# qdr2_3.net
KiCad netlist of a schematic drawn in Altium Designer
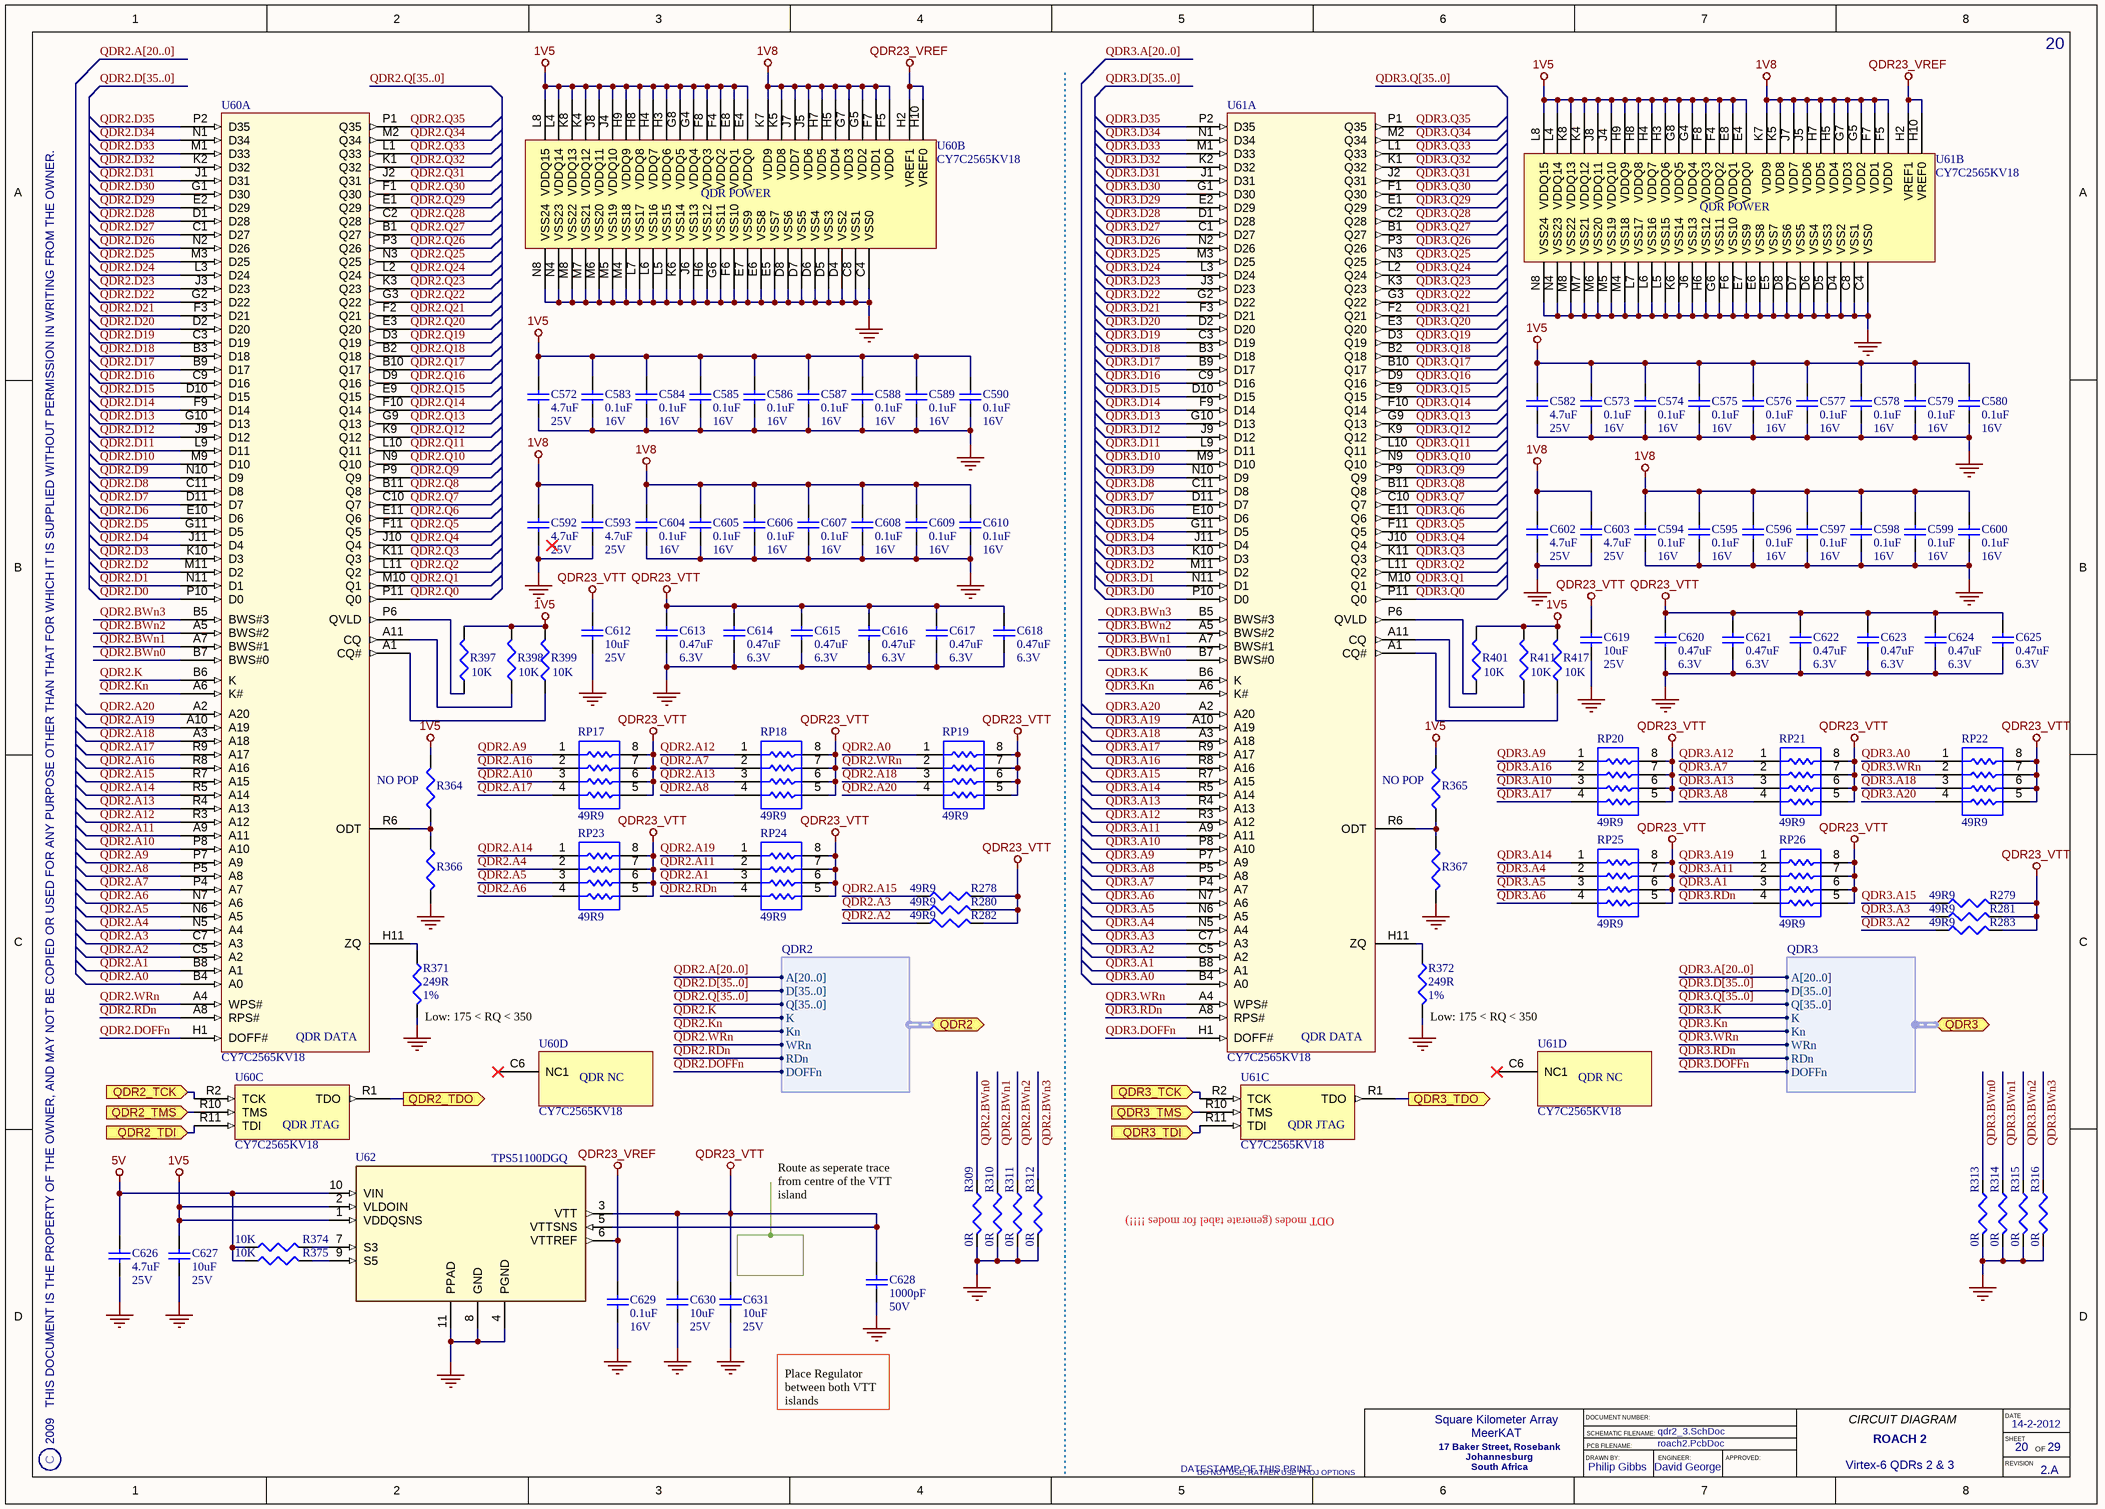
[diagram p0: qdr2_3.SchDoc]

(export (version "E")
  (design (tool "Eeschema 10.0.6"))
  (components
    (comp (ref "C572")
      (value "4.7uF")
      (footprint "CAPC2012X127L")
      (description "4.7uF, Ceramic Capacitor")
      (fields
        (field (name "RATING") "25V")
        (field (name "MANUFACTURER") "MURATA")
        (field (name "PARTNUM") "GRM21BR61E475KA12K")
      )
      (libsource (lib "altium_db") (part "CapStd"))
    )
    (comp (ref "C573")
      (value "0.1uF")
      (footprint "CAPC1005X60L")
      (description "0.1uF, Ceramic Capacitor")
      (fields
        (field (name "RATING") "16V")
        (field (name "MANUFACTURER") "VENKEL")
        (field (name "PARTNUM") "C0402X7R160-104KN")
      )
      (libsource (lib "altium_db") (part "CapStd"))
    )
    (comp (ref "C574")
      (value "0.1uF")
      (footprint "CAPC1005X60L")
      (description "0.1uF, Ceramic Capacitor")
      (fields
        (field (name "RATING") "16V")
        (field (name "MANUFACTURER") "VENKEL")
        (field (name "PARTNUM") "C0402X7R160-104KN")
      )
      (libsource (lib "altium_db") (part "CapStd"))
    )
    (comp (ref "C575")
      (value "0.1uF")
      (footprint "CAPC1005X60L")
      (description "0.1uF, Ceramic Capacitor")
      (fields
        (field (name "RATING") "16V")
        (field (name "MANUFACTURER") "VENKEL")
        (field (name "PARTNUM") "C0402X7R160-104KN")
      )
      (libsource (lib "altium_db") (part "CapStd"))
    )
    (comp (ref "C576")
      (value "0.1uF")
      (footprint "CAPC1005X60L")
      (description "0.1uF, Ceramic Capacitor")
      (fields
        (field (name "RATING") "16V")
        (field (name "MANUFACTURER") "VENKEL")
        (field (name "PARTNUM") "C0402X7R160-104KN")
      )
      (libsource (lib "altium_db") (part "CapStd"))
    )
    (comp (ref "C577")
      (value "0.1uF")
      (footprint "CAPC1005X60L")
      (description "0.1uF, Ceramic Capacitor")
      (fields
        (field (name "RATING") "16V")
        (field (name "MANUFACTURER") "VENKEL")
        (field (name "PARTNUM") "C0402X7R160-104KN")
      )
      (libsource (lib "altium_db") (part "CapStd"))
    )
    (comp (ref "C578")
      (value "0.1uF")
      (footprint "CAPC1005X60L")
      (description "0.1uF, Ceramic Capacitor")
      (fields
        (field (name "RATING") "16V")
        (field (name "MANUFACTURER") "VENKEL")
        (field (name "PARTNUM") "C0402X7R160-104KN")
      )
      (libsource (lib "altium_db") (part "CapStd"))
    )
    (comp (ref "C579")
      (value "0.1uF")
      (footprint "CAPC1005X60L")
      (description "0.1uF, Ceramic Capacitor")
      (fields
        (field (name "RATING") "16V")
        (field (name "MANUFACTURER") "VENKEL")
        (field (name "PARTNUM") "C0402X7R160-104KN")
      )
      (libsource (lib "altium_db") (part "CapStd"))
    )
    (comp (ref "C580")
      (value "0.1uF")
      (footprint "CAPC1005X60L")
      (description "0.1uF, Ceramic Capacitor")
      (fields
        (field (name "RATING") "16V")
        (field (name "MANUFACTURER") "VENKEL")
        (field (name "PARTNUM") "C0402X7R160-104KN")
      )
      (libsource (lib "altium_db") (part "CapStd"))
    )
    (comp (ref "C582")
      (value "4.7uF")
      (footprint "CAPC2012X127L")
      (description "4.7uF, Ceramic Capacitor")
      (fields
        (field (name "RATING") "25V")
        (field (name "MANUFACTURER") "MURATA")
        (field (name "PARTNUM") "GRM21BR61E475KA12K")
      )
      (libsource (lib "altium_db") (part "CapStd"))
    )
    (comp (ref "C583")
      (value "0.1uF")
      (footprint "CAPC1005X60L")
      (description "0.1uF, Ceramic Capacitor")
      (fields
        (field (name "RATING") "16V")
        (field (name "MANUFACTURER") "VENKEL")
        (field (name "PARTNUM") "C0402X7R160-104KN")
      )
      (libsource (lib "altium_db") (part "CapStd"))
    )
    (comp (ref "C584")
      (value "0.1uF")
      (footprint "CAPC1005X60L")
      (description "0.1uF, Ceramic Capacitor")
      (fields
        (field (name "RATING") "16V")
        (field (name "MANUFACTURER") "VENKEL")
        (field (name "PARTNUM") "C0402X7R160-104KN")
      )
      (libsource (lib "altium_db") (part "CapStd"))
    )
    (comp (ref "C585")
      (value "0.1uF")
      (footprint "CAPC1005X60L")
      (description "0.1uF, Ceramic Capacitor")
      (fields
        (field (name "RATING") "16V")
        (field (name "MANUFACTURER") "VENKEL")
        (field (name "PARTNUM") "C0402X7R160-104KN")
      )
      (libsource (lib "altium_db") (part "CapStd"))
    )
    (comp (ref "C586")
      (value "0.1uF")
      (footprint "CAPC1005X60L")
      (description "0.1uF, Ceramic Capacitor")
      (fields
        (field (name "RATING") "16V")
        (field (name "MANUFACTURER") "VENKEL")
        (field (name "PARTNUM") "C0402X7R160-104KN")
      )
      (libsource (lib "altium_db") (part "CapStd"))
    )
    (comp (ref "C587")
      (value "0.1uF")
      (footprint "CAPC1005X60L")
      (description "0.1uF, Ceramic Capacitor")
      (fields
        (field (name "RATING") "16V")
        (field (name "MANUFACTURER") "VENKEL")
        (field (name "PARTNUM") "C0402X7R160-104KN")
      )
      (libsource (lib "altium_db") (part "CapStd"))
    )
    (comp (ref "C588")
      (value "0.1uF")
      (footprint "CAPC1005X60L")
      (description "0.1uF, Ceramic Capacitor")
      (fields
        (field (name "RATING") "16V")
        (field (name "MANUFACTURER") "VENKEL")
        (field (name "PARTNUM") "C0402X7R160-104KN")
      )
      (libsource (lib "altium_db") (part "CapStd"))
    )
    (comp (ref "C589")
      (value "0.1uF")
      (footprint "CAPC1005X60L")
      (description "0.1uF, Ceramic Capacitor")
      (fields
        (field (name "RATING") "16V")
        (field (name "MANUFACTURER") "VENKEL")
        (field (name "PARTNUM") "C0402X7R160-104KN")
      )
      (libsource (lib "altium_db") (part "CapStd"))
    )
    (comp (ref "C590")
      (value "0.1uF")
      (footprint "CAPC1005X60L")
      (description "0.1uF, Ceramic Capacitor")
      (fields
        (field (name "RATING") "16V")
        (field (name "MANUFACTURER") "VENKEL")
        (field (name "PARTNUM") "C0402X7R160-104KN")
      )
      (libsource (lib "altium_db") (part "CapStd"))
    )
    (comp (ref "C592")
      (value "4.7uF")
      (footprint "CAPC2012X127L")
      (description "4.7uF, Ceramic Capacitor")
      (fields
        (field (name "RATING") "25V")
        (field (name "MANUFACTURER") "MURATA")
        (field (name "PARTNUM") "GRM21BR61E475KA12K")
      )
      (libsource (lib "altium_db") (part "CapStd"))
    )
    (comp (ref "C593")
      (value "4.7uF")
      (footprint "CAPC2012X127L")
      (description "4.7uF, Ceramic Capacitor")
      (fields
        (field (name "RATING") "25V")
        (field (name "MANUFACTURER") "MURATA")
        (field (name "PARTNUM") "GRM21BR61E475KA12K")
      )
      (libsource (lib "altium_db") (part "CapStd"))
    )
    (comp (ref "C594")
      (value "0.1uF")
      (footprint "CAPC1005X60L")
      (description "0.1uF, Ceramic Capacitor")
      (fields
        (field (name "RATING") "16V")
        (field (name "MANUFACTURER") "VENKEL")
        (field (name "PARTNUM") "C0402X7R160-104KN")
      )
      (libsource (lib "altium_db") (part "CapStd"))
    )
    (comp (ref "C595")
      (value "0.1uF")
      (footprint "CAPC1005X60L")
      (description "0.1uF, Ceramic Capacitor")
      (fields
        (field (name "RATING") "16V")
        (field (name "MANUFACTURER") "VENKEL")
        (field (name "PARTNUM") "C0402X7R160-104KN")
      )
      (libsource (lib "altium_db") (part "CapStd"))
    )
    (comp (ref "C596")
      (value "0.1uF")
      (footprint "CAPC1005X60L")
      (description "0.1uF, Ceramic Capacitor")
      (fields
        (field (name "RATING") "16V")
        (field (name "MANUFACTURER") "VENKEL")
        (field (name "PARTNUM") "C0402X7R160-104KN")
      )
      (libsource (lib "altium_db") (part "CapStd"))
    )
    (comp (ref "C597")
      (value "0.1uF")
      (footprint "CAPC1005X60L")
      (description "0.1uF, Ceramic Capacitor")
      (fields
        (field (name "RATING") "16V")
        (field (name "MANUFACTURER") "VENKEL")
        (field (name "PARTNUM") "C0402X7R160-104KN")
      )
      (libsource (lib "altium_db") (part "CapStd"))
    )
    (comp (ref "C598")
      (value "0.1uF")
      (footprint "CAPC1005X60L")
      (description "0.1uF, Ceramic Capacitor")
      (fields
        (field (name "RATING") "16V")
        (field (name "MANUFACTURER") "VENKEL")
        (field (name "PARTNUM") "C0402X7R160-104KN")
      )
      (libsource (lib "altium_db") (part "CapStd"))
    )
    (comp (ref "C599")
      (value "0.1uF")
      (footprint "CAPC1005X60L")
      (description "0.1uF, Ceramic Capacitor")
      (fields
        (field (name "RATING") "16V")
        (field (name "MANUFACTURER") "VENKEL")
        (field (name "PARTNUM") "C0402X7R160-104KN")
      )
      (libsource (lib "altium_db") (part "CapStd"))
    )
    (comp (ref "C600")
      (value "0.1uF")
      (footprint "CAPC1005X60L")
      (description "0.1uF, Ceramic Capacitor")
      (fields
        (field (name "RATING") "16V")
        (field (name "MANUFACTURER") "VENKEL")
        (field (name "PARTNUM") "C0402X7R160-104KN")
      )
      (libsource (lib "altium_db") (part "CapStd"))
    )
    (comp (ref "C602")
      (value "4.7uF")
      (footprint "CAPC2012X127L")
      (description "4.7uF, Ceramic Capacitor")
      (fields
        (field (name "RATING") "25V")
        (field (name "MANUFACTURER") "MURATA")
        (field (name "PARTNUM") "GRM21BR61E475KA12K")
      )
      (libsource (lib "altium_db") (part "CapStd"))
    )
    (comp (ref "C603")
      (value "4.7uF")
      (footprint "CAPC2012X127L")
      (description "4.7uF, Ceramic Capacitor")
      (fields
        (field (name "RATING") "25V")
        (field (name "MANUFACTURER") "MURATA")
        (field (name "PARTNUM") "GRM21BR61E475KA12K")
      )
      (libsource (lib "altium_db") (part "CapStd"))
    )
    (comp (ref "C604")
      (value "0.1uF")
      (footprint "CAPC1005X60L")
      (description "0.1uF, Ceramic Capacitor")
      (fields
        (field (name "RATING") "16V")
        (field (name "MANUFACTURER") "VENKEL")
        (field (name "PARTNUM") "C0402X7R160-104KN")
      )
      (libsource (lib "altium_db") (part "CapStd"))
    )
    (comp (ref "C605")
      (value "0.1uF")
      (footprint "CAPC1005X60L")
      (description "0.1uF, Ceramic Capacitor")
      (fields
        (field (name "RATING") "16V")
        (field (name "MANUFACTURER") "VENKEL")
        (field (name "PARTNUM") "C0402X7R160-104KN")
      )
      (libsource (lib "altium_db") (part "CapStd"))
    )
    (comp (ref "C606")
      (value "0.1uF")
      (footprint "CAPC1005X60L")
      (description "0.1uF, Ceramic Capacitor")
      (fields
        (field (name "RATING") "16V")
        (field (name "MANUFACTURER") "VENKEL")
        (field (name "PARTNUM") "C0402X7R160-104KN")
      )
      (libsource (lib "altium_db") (part "CapStd"))
    )
    (comp (ref "C607")
      (value "0.1uF")
      (footprint "CAPC1005X60L")
      (description "0.1uF, Ceramic Capacitor")
      (fields
        (field (name "RATING") "16V")
        (field (name "MANUFACTURER") "VENKEL")
        (field (name "PARTNUM") "C0402X7R160-104KN")
      )
      (libsource (lib "altium_db") (part "CapStd"))
    )
    (comp (ref "C608")
      (value "0.1uF")
      (footprint "CAPC1005X60L")
      (description "0.1uF, Ceramic Capacitor")
      (fields
        (field (name "RATING") "16V")
        (field (name "MANUFACTURER") "VENKEL")
        (field (name "PARTNUM") "C0402X7R160-104KN")
      )
      (libsource (lib "altium_db") (part "CapStd"))
    )
    (comp (ref "C609")
      (value "0.1uF")
      (footprint "CAPC1005X60L")
      (description "0.1uF, Ceramic Capacitor")
      (fields
        (field (name "RATING") "16V")
        (field (name "MANUFACTURER") "VENKEL")
        (field (name "PARTNUM") "C0402X7R160-104KN")
      )
      (libsource (lib "altium_db") (part "CapStd"))
    )
    (comp (ref "C610")
      (value "0.1uF")
      (footprint "CAPC1005X60L")
      (description "0.1uF, Ceramic Capacitor")
      (fields
        (field (name "RATING") "16V")
        (field (name "MANUFACTURER") "VENKEL")
        (field (name "PARTNUM") "C0402X7R160-104KN")
      )
      (libsource (lib "altium_db") (part "CapStd"))
    )
    (comp (ref "C612")
      (value "10uF")
      (footprint "CAPC3225X200L")
      (description "10uF, Ceramic Capacitor")
      (fields
        (field (name "RATING") "25V")
        (field (name "MANUFACTURER") "MURATA")
        (field (name "PARTNUM") "GRM32DR61E106KA12L")
      )
      (libsource (lib "altium_db") (part "CapStd"))
    )
    (comp (ref "C613")
      (value "0.47uF")
      (footprint "CAPC1005X55L")
      (description "0.47uF, Ceramic Capacitor")
      (fields
        (field (name "RATING") "6.3V")
        (field (name "MANUFACTURER") "MURATA")
        (field (name "PARTNUM") "GRM155R60J474KE19")
      )
      (libsource (lib "altium_db") (part "CapStd"))
    )
    (comp (ref "C614")
      (value "0.47uF")
      (footprint "CAPC1005X55L")
      (description "0.47uF, Ceramic Capacitor")
      (fields
        (field (name "RATING") "6.3V")
        (field (name "MANUFACTURER") "MURATA")
        (field (name "PARTNUM") "GRM155R60J474KE19")
      )
      (libsource (lib "altium_db") (part "CapStd"))
    )
    (comp (ref "C615")
      (value "0.47uF")
      (footprint "CAPC1005X55L")
      (description "0.47uF, Ceramic Capacitor")
      (fields
        (field (name "RATING") "6.3V")
        (field (name "MANUFACTURER") "MURATA")
        (field (name "PARTNUM") "GRM155R60J474KE19")
      )
      (libsource (lib "altium_db") (part "CapStd"))
    )
    (comp (ref "C616")
      (value "0.47uF")
      (footprint "CAPC1005X55L")
      (description "0.47uF, Ceramic Capacitor")
      (fields
        (field (name "RATING") "6.3V")
        (field (name "MANUFACTURER") "MURATA")
        (field (name "PARTNUM") "GRM155R60J474KE19")
      )
      (libsource (lib "altium_db") (part "CapStd"))
    )
    (comp (ref "C617")
      (value "0.47uF")
      (footprint "CAPC1005X55L")
      (description "0.47uF, Ceramic Capacitor")
      (fields
        (field (name "RATING") "6.3V")
        (field (name "MANUFACTURER") "MURATA")
        (field (name "PARTNUM") "GRM155R60J474KE19")
      )
      (libsource (lib "altium_db") (part "CapStd"))
    )
    (comp (ref "C618")
      (value "0.47uF")
      (footprint "CAPC1005X55L")
      (description "0.47uF, Ceramic Capacitor")
      (fields
        (field (name "RATING") "6.3V")
        (field (name "MANUFACTURER") "MURATA")
        (field (name "PARTNUM") "GRM155R60J474KE19")
      )
      (libsource (lib "altium_db") (part "CapStd"))
    )
    (comp (ref "C619")
      (value "10uF")
      (footprint "CAPC3225X200L")
      (description "10uF, Ceramic Capacitor")
      (fields
        (field (name "RATING") "25V")
        (field (name "MANUFACTURER") "MURATA")
        (field (name "PARTNUM") "GRM32DR61E106KA12L")
      )
      (libsource (lib "altium_db") (part "CapStd"))
    )
    (comp (ref "C620")
      (value "0.47uF")
      (footprint "CAPC1005X55L")
      (description "0.47uF, Ceramic Capacitor")
      (fields
        (field (name "RATING") "6.3V")
        (field (name "MANUFACTURER") "MURATA")
        (field (name "PARTNUM") "GRM155R60J474KE19")
      )
      (libsource (lib "altium_db") (part "CapStd"))
    )
    (comp (ref "C621")
      (value "0.47uF")
      (footprint "CAPC1005X55L")
      (description "0.47uF, Ceramic Capacitor")
      (fields
        (field (name "RATING") "6.3V")
        (field (name "MANUFACTURER") "MURATA")
        (field (name "PARTNUM") "GRM155R60J474KE19")
      )
      (libsource (lib "altium_db") (part "CapStd"))
    )
    (comp (ref "C622")
      (value "0.47uF")
      (footprint "CAPC1005X55L")
      (description "0.47uF, Ceramic Capacitor")
      (fields
        (field (name "RATING") "6.3V")
        (field (name "MANUFACTURER") "MURATA")
        (field (name "PARTNUM") "GRM155R60J474KE19")
      )
      (libsource (lib "altium_db") (part "CapStd"))
    )
    (comp (ref "C623")
      (value "0.47uF")
      (footprint "CAPC1005X55L")
      (description "0.47uF, Ceramic Capacitor")
      (fields
        (field (name "RATING") "6.3V")
        (field (name "MANUFACTURER") "MURATA")
        (field (name "PARTNUM") "GRM155R60J474KE19")
      )
      (libsource (lib "altium_db") (part "CapStd"))
    )
    (comp (ref "C624")
      (value "0.47uF")
      (footprint "CAPC1005X55L")
      (description "0.47uF, Ceramic Capacitor")
      (fields
        (field (name "RATING") "6.3V")
        (field (name "MANUFACTURER") "MURATA")
        (field (name "PARTNUM") "GRM155R60J474KE19")
      )
      (libsource (lib "altium_db") (part "CapStd"))
    )
    (comp (ref "C625")
      (value "0.47uF")
      (footprint "CAPC1005X55L")
      (description "0.47uF, Ceramic Capacitor")
      (fields
        (field (name "RATING") "6.3V")
        (field (name "MANUFACTURER") "MURATA")
        (field (name "PARTNUM") "GRM155R60J474KE19")
      )
      (libsource (lib "altium_db") (part "CapStd"))
    )
    (comp (ref "C626")
      (value "4.7uF")
      (footprint "CAPC2012X127L")
      (description "4.7uF, Ceramic Capacitor")
      (fields
        (field (name "RATING") "25V")
        (field (name "MANUFACTURER") "MURATA")
        (field (name "PARTNUM") "GRM21BR61E475KA12K")
      )
      (libsource (lib "altium_db") (part "CapStd"))
    )
    (comp (ref "C627")
      (value "10uF")
      (footprint "CAPC3225X200L")
      (description "10uF, Ceramic Capacitor")
      (fields
        (field (name "RATING") "25V")
        (field (name "MANUFACTURER") "MURATA")
        (field (name "PARTNUM") "GRM32DR61E106KA12L")
      )
      (libsource (lib "altium_db") (part "CapStd"))
    )
    (comp (ref "C628")
      (value "1000pF")
      (footprint "CAPC1005X55L")
      (description "1000pF, Ceramic Capacitor")
      (fields
        (field (name "RATING") "50V")
        (field (name "MANUFACTURER") "MURATA")
        (field (name "PARTNUM") "GRM155R61H102KA01D")
      )
      (libsource (lib "altium_db") (part "CapStd"))
    )
    (comp (ref "C629")
      (value "0.1uF")
      (footprint "CAPC1005X60L")
      (description "0.1uF, Ceramic Capacitor")
      (fields
        (field (name "RATING") "16V")
        (field (name "MANUFACTURER") "VENKEL")
        (field (name "PARTNUM") "C0402X7R160-104KN")
      )
      (libsource (lib "altium_db") (part "CapStd"))
    )
    (comp (ref "C630")
      (value "10uF")
      (footprint "CAPC3225X200L")
      (description "10uF, Ceramic Capacitor")
      (fields
        (field (name "RATING") "25V")
        (field (name "MANUFACTURER") "MURATA")
        (field (name "PARTNUM") "GRM32DR61E106KA12L")
      )
      (libsource (lib "altium_db") (part "CapStd"))
    )
    (comp (ref "C631")
      (value "10uF")
      (footprint "CAPC3225X200L")
      (description "10uF, Ceramic Capacitor")
      (fields
        (field (name "RATING") "25V")
        (field (name "MANUFACTURER") "MURATA")
        (field (name "PARTNUM") "GRM32DR61E106KA12L")
      )
      (libsource (lib "altium_db") (part "CapStd"))
    )
    (comp (ref "R278")
      (value "49R9")
      (footprint "RESC1005X40L")
      (description "49R9, 1.1mm x 0.5mm, Thick Film Resistor")
      (fields (field (name "MANUFACTURER") "ROYALOHM") (field (name "PARTNUM") "0402WGF499JT1E"))
      (libsource (lib "altium_db") (part "ResStd"))
    )
    (comp (ref "R279")
      (value "49R9")
      (footprint "RESC1005X40L")
      (description "49R9, 1.1mm x 0.5mm, Thick Film Resistor")
      (fields (field (name "MANUFACTURER") "ROYALOHM") (field (name "PARTNUM") "0402WGF499JT1E"))
      (libsource (lib "altium_db") (part "ResStd"))
    )
    (comp (ref "R280")
      (value "49R9")
      (footprint "RESC1005X40L")
      (description "49R9, 1.1mm x 0.5mm, Thick Film Resistor")
      (fields (field (name "MANUFACTURER") "ROYALOHM") (field (name "PARTNUM") "0402WGF499JT1E"))
      (libsource (lib "altium_db") (part "ResStd"))
    )
    (comp (ref "R281")
      (value "49R9")
      (footprint "RESC1005X40L")
      (description "49R9, 1.1mm x 0.5mm, Thick Film Resistor")
      (fields (field (name "MANUFACTURER") "ROYALOHM") (field (name "PARTNUM") "0402WGF499JT1E"))
      (libsource (lib "altium_db") (part "ResStd"))
    )
    (comp (ref "R282")
      (value "49R9")
      (footprint "RESC1005X40L")
      (description "49R9, 1.1mm x 0.5mm, Thick Film Resistor")
      (fields (field (name "MANUFACTURER") "ROYALOHM") (field (name "PARTNUM") "0402WGF499JT1E"))
      (libsource (lib "altium_db") (part "ResStd"))
    )
    (comp (ref "R283")
      (value "49R9")
      (footprint "RESC1005X40L")
      (description "49R9, 1.1mm x 0.5mm, Thick Film Resistor")
      (fields (field (name "MANUFACTURER") "ROYALOHM") (field (name "PARTNUM") "0402WGF499JT1E"))
      (libsource (lib "altium_db") (part "ResStd"))
    )
    (comp (ref "R309")
      (value "0R")
      (footprint "RESC1005X40L")
      (description "0R, 1.1mm x 0.5mm, Thick Film Resistor")
      (fields (field (name "MANUFACTURER") "ROYALOHM") (field (name "PARTNUM") "0402WG00000T1E"))
      (libsource (lib "altium_db") (part "ResStd"))
    )
    (comp (ref "R310")
      (value "0R")
      (footprint "RESC1005X40L")
      (description "0R, 1.1mm x 0.5mm, Thick Film Resistor")
      (fields (field (name "MANUFACTURER") "ROYALOHM") (field (name "PARTNUM") "0402WG00000T1E"))
      (libsource (lib "altium_db") (part "ResStd"))
    )
    (comp (ref "R311")
      (value "0R")
      (footprint "RESC1005X40L")
      (description "0R, 1.1mm x 0.5mm, Thick Film Resistor")
      (fields (field (name "MANUFACTURER") "ROYALOHM") (field (name "PARTNUM") "0402WG00000T1E"))
      (libsource (lib "altium_db") (part "ResStd"))
    )
    (comp (ref "R312")
      (value "0R")
      (footprint "RESC1005X40L")
      (description "0R, 1.1mm x 0.5mm, Thick Film Resistor")
      (fields (field (name "MANUFACTURER") "ROYALOHM") (field (name "PARTNUM") "0402WG00000T1E"))
      (libsource (lib "altium_db") (part "ResStd"))
    )
    (comp (ref "R313")
      (value "0R")
      (footprint "RESC1005X40L")
      (description "0R, 1.1mm x 0.5mm, Thick Film Resistor")
      (fields (field (name "MANUFACTURER") "ROYALOHM") (field (name "PARTNUM") "0402WG00000T1E"))
      (libsource (lib "altium_db") (part "ResStd"))
    )
    (comp (ref "R314")
      (value "0R")
      (footprint "RESC1005X40L")
      (description "0R, 1.1mm x 0.5mm, Thick Film Resistor")
      (fields (field (name "MANUFACTURER") "ROYALOHM") (field (name "PARTNUM") "0402WG00000T1E"))
      (libsource (lib "altium_db") (part "ResStd"))
    )
    (comp (ref "R315")
      (value "0R")
      (footprint "RESC1005X40L")
      (description "0R, 1.1mm x 0.5mm, Thick Film Resistor")
      (fields (field (name "MANUFACTURER") "ROYALOHM") (field (name "PARTNUM") "0402WG00000T1E"))
      (libsource (lib "altium_db") (part "ResStd"))
    )
    (comp (ref "R316")
      (value "0R")
      (footprint "RESC1005X40L")
      (description "0R, 1.1mm x 0.5mm, Thick Film Resistor")
      (fields (field (name "MANUFACTURER") "ROYALOHM") (field (name "PARTNUM") "0402WG00000T1E"))
      (libsource (lib "altium_db") (part "ResStd"))
    )
    (comp (ref "R364")
      (value "10K")
      (footprint "RESC1005X40L")
      (description "10K, 1.1mm x 0.5mm, Thick Film Resistor")
      (fields (field (name "MANUFACTURER") "ROYALOHM") (field (name "PARTNUM") "0402WGJ0103T1E"))
      (libsource (lib "altium_db") (part "ResStd"))
    )
    (comp (ref "R365")
      (value "10K")
      (footprint "RESC1005X40L")
      (description "10K, 1.1mm x 0.5mm, Thick Film Resistor")
      (fields (field (name "MANUFACTURER") "ROYALOHM") (field (name "PARTNUM") "0402WGJ0103T1E"))
      (libsource (lib "altium_db") (part "ResStd"))
    )
    (comp (ref "R366")
      (value "10K")
      (footprint "RESC1005X40L")
      (description "10K, 1.1mm x 0.5mm, Thick Film Resistor")
      (fields (field (name "MANUFACTURER") "ROYALOHM") (field (name "PARTNUM") "0402WGJ0103T1E"))
      (libsource (lib "altium_db") (part "ResStd"))
    )
    (comp (ref "R367")
      (value "10K")
      (footprint "RESC1005X40L")
      (description "10K, 1.1mm x 0.5mm, Thick Film Resistor")
      (fields (field (name "MANUFACTURER") "ROYALOHM") (field (name "PARTNUM") "0402WGJ0103T1E"))
      (libsource (lib "altium_db") (part "ResStd"))
    )
    (comp (ref "R371")
      (value "249R")
      (footprint "RESC1005X40L")
      (description "249R, 1.1mm x 0.5mm, Thick Film Resistor")
      (fields
        (field (name "MANUFACTURER") "ROYALOHM")
        (field (name "PARTNUM") "0402WGF2490T1E")
        (field (name "TOLERANCE") "1%")
      )
      (libsource (lib "altium_db") (part "ResStd"))
    )
    (comp (ref "R372")
      (value "249R")
      (footprint "RESC1005X40L")
      (description "249R, 1.1mm x 0.5mm, Thick Film Resistor")
      (fields
        (field (name "MANUFACTURER") "ROYALOHM")
        (field (name "PARTNUM") "0402WGF2490T1E")
        (field (name "TOLERANCE") "1%")
      )
      (libsource (lib "altium_db") (part "ResStd"))
    )
    (comp (ref "R374")
      (value "10K")
      (footprint "RESC1005X40L")
      (description "10K, 1.1mm x 0.5mm, Thick Film Resistor")
      (fields (field (name "MANUFACTURER") "ROYALOHM") (field (name "PARTNUM") "0402WGJ0103T1E"))
      (libsource (lib "altium_db") (part "ResStd"))
    )
    (comp (ref "R375")
      (value "10K")
      (footprint "RESC1005X40L")
      (description "10K, 1.1mm x 0.5mm, Thick Film Resistor")
      (fields (field (name "MANUFACTURER") "ROYALOHM") (field (name "PARTNUM") "0402WGJ0103T1E"))
      (libsource (lib "altium_db") (part "ResStd"))
    )
    (comp (ref "R397")
      (value "10K")
      (footprint "RESC1005X40L")
      (description "10K, 1.1mm x 0.5mm, Thick Film Resistor")
      (fields (field (name "MANUFACTURER") "ROYALOHM") (field (name "PARTNUM") "0402WGJ0103T1E"))
      (libsource (lib "altium_db") (part "ResStd"))
    )
    (comp (ref "R398")
      (value "10K")
      (footprint "RESC1005X40L")
      (description "10K, 1.1mm x 0.5mm, Thick Film Resistor")
      (fields (field (name "MANUFACTURER") "ROYALOHM") (field (name "PARTNUM") "0402WGJ0103T1E"))
      (libsource (lib "altium_db") (part "ResStd"))
    )
    (comp (ref "R399")
      (value "10K")
      (footprint "RESC1005X40L")
      (description "10K, 1.1mm x 0.5mm, Thick Film Resistor")
      (fields (field (name "MANUFACTURER") "ROYALOHM") (field (name "PARTNUM") "0402WGJ0103T1E"))
      (libsource (lib "altium_db") (part "ResStd"))
    )
    (comp (ref "R401")
      (value "10K")
      (footprint "RESC1005X40L")
      (description "10K, 1.1mm x 0.5mm, Thick Film Resistor")
      (fields (field (name "MANUFACTURER") "ROYALOHM") (field (name "PARTNUM") "0402WGJ0103T1E"))
      (libsource (lib "altium_db") (part "ResStd"))
    )
    (comp (ref "R411")
      (value "10K")
      (footprint "RESC1005X40L")
      (description "10K, 1.1mm x 0.5mm, Thick Film Resistor")
      (fields (field (name "MANUFACTURER") "ROYALOHM") (field (name "PARTNUM") "0402WGJ0103T1E"))
      (libsource (lib "altium_db") (part "ResStd"))
    )
    (comp (ref "R417")
      (value "10K")
      (footprint "RESC1005X40L")
      (description "10K, 1.1mm x 0.5mm, Thick Film Resistor")
      (fields (field (name "MANUFACTURER") "ROYALOHM") (field (name "PARTNUM") "0402WGJ0103T1E"))
      (libsource (lib "altium_db") (part "ResStd"))
    )
    (comp (ref "RP17")
      (value "49R9")
      (footprint "RESCAV50P100X200X45-8L")
      (description "4-Wide, Isolated, Thick Film Resistor Network")
      (fields (field (name "MANUFACTURER") "ROYALOHM") (field (name "PARTNUM") "4D02WGJ0510B1E"))
      (libsource (lib "altium_db") (part "ResPack4"))
    )
    (comp (ref "RP18")
      (value "49R9")
      (footprint "RESCAV50P100X200X45-8L")
      (description "4-Wide, Isolated, Thick Film Resistor Network")
      (fields (field (name "MANUFACTURER") "ROYALOHM") (field (name "PARTNUM") "4D02WGJ0510B1E"))
      (libsource (lib "altium_db") (part "ResPack4"))
    )
    (comp (ref "RP19")
      (value "49R9")
      (footprint "RESCAV50P100X200X45-8L")
      (description "4-Wide, Isolated, Thick Film Resistor Network")
      (fields (field (name "MANUFACTURER") "ROYALOHM") (field (name "PARTNUM") "4D02WGJ0510B1E"))
      (libsource (lib "altium_db") (part "ResPack4"))
    )
    (comp (ref "RP20")
      (value "49R9")
      (footprint "RESCAV50P100X200X45-8L")
      (description "4-Wide, Isolated, Thick Film Resistor Network")
      (fields (field (name "MANUFACTURER") "ROYALOHM") (field (name "PARTNUM") "4D02WGJ0510B1E"))
      (libsource (lib "altium_db") (part "ResPack4"))
    )
    (comp (ref "RP21")
      (value "49R9")
      (footprint "RESCAV50P100X200X45-8L")
      (description "4-Wide, Isolated, Thick Film Resistor Network")
      (fields (field (name "MANUFACTURER") "ROYALOHM") (field (name "PARTNUM") "4D02WGJ0510B1E"))
      (libsource (lib "altium_db") (part "ResPack4"))
    )
    (comp (ref "RP22")
      (value "49R9")
      (footprint "RESCAV50P100X200X45-8L")
      (description "4-Wide, Isolated, Thick Film Resistor Network")
      (fields (field (name "MANUFACTURER") "ROYALOHM") (field (name "PARTNUM") "4D02WGJ0510B1E"))
      (libsource (lib "altium_db") (part "ResPack4"))
    )
    (comp (ref "RP23")
      (value "49R9")
      (footprint "RESCAV50P100X200X45-8L")
      (description "4-Wide, Isolated, Thick Film Resistor Network")
      (fields (field (name "MANUFACTURER") "ROYALOHM") (field (name "PARTNUM") "4D02WGJ0510B1E"))
      (libsource (lib "altium_db") (part "ResPack4"))
    )
    (comp (ref "RP24")
      (value "49R9")
      (footprint "RESCAV50P100X200X45-8L")
      (description "4-Wide, Isolated, Thick Film Resistor Network")
      (fields (field (name "MANUFACTURER") "ROYALOHM") (field (name "PARTNUM") "4D02WGJ0510B1E"))
      (libsource (lib "altium_db") (part "ResPack4"))
    )
    (comp (ref "RP25")
      (value "49R9")
      (footprint "RESCAV50P100X200X45-8L")
      (description "4-Wide, Isolated, Thick Film Resistor Network")
      (fields (field (name "MANUFACTURER") "ROYALOHM") (field (name "PARTNUM") "4D02WGJ0510B1E"))
      (libsource (lib "altium_db") (part "ResPack4"))
    )
    (comp (ref "RP26")
      (value "49R9")
      (footprint "RESCAV50P100X200X45-8L")
      (description "4-Wide, Isolated, Thick Film Resistor Network")
      (fields (field (name "MANUFACTURER") "ROYALOHM") (field (name "PARTNUM") "4D02WGJ0510B1E"))
      (libsource (lib "altium_db") (part "ResPack4"))
    )
    (comp (ref "U60")
      (value "CY7C2565KV18")
      (footprint "FBGA_165-Ball")
      (description "72Mb, 36-Bit wide, QDR2+ Synchronous SRAM with ODT")
      (fields (field (name "MANUFACTURER") "Cypress") (field (name "PARTNUM") "CY7C2565KV18-450BZXC"))
      (libsource (lib "altium_db") (part "QDR2PLUS_36BIT"))
    )
    (comp (ref "U61")
      (value "CY7C2565KV18")
      (footprint "FBGA_165-Ball")
      (description "72Mb, 36-Bit wide, QDR2+ Synchronous SRAM with ODT")
      (fields (field (name "MANUFACTURER") "Cypress") (field (name "PARTNUM") "CY7C2565KV18-450BZXC"))
      (libsource (lib "altium_db") (part "QDR2PLUS_36BIT"))
    )
    (comp (ref "U62")
      (value "TPS51100DGQ")
      (footprint "MSOP_10-N")
      (description "3A Sink/Source Regulator")
      (fields (field (name "MANUFACTURER") "Texas Instruments"))
      (libsource (lib "altium_db") (part "TPS51100DGQ"))
    )
  )
  (nets
    (net (code "3") (name "/QDR2.A0") (class "Default")
      (node (ref "RP19") (pin "1") (pinfunction "1_1") (pintype "passive"))
      (node (ref "U60") (pin "B4") (pinfunction "A0_B4") (pintype "input"))
    )
    (net (code "4") (name "/QDR2.A1") (class "Default")
      (node (ref "RP24") (pin "3") (pinfunction "3_3") (pintype "passive"))
      (node (ref "U60") (pin "B8") (pinfunction "A1_B8") (pintype "input"))
    )
    (net (code "5") (name "/QDR2.A2") (class "Default")
      (node (ref "R282") (pin "1") (pinfunction "1_1") (pintype "passive"))
      (node (ref "U60") (pin "C5") (pinfunction "A2_C5") (pintype "input"))
    )
    (net (code "6") (name "/QDR2.A3") (class "Default")
      (node (ref "R280") (pin "1") (pinfunction "1_1") (pintype "passive"))
      (node (ref "U60") (pin "C7") (pinfunction "A3_C7") (pintype "input"))
    )
    (net (code "7") (name "/QDR2.A4") (class "Default")
      (node (ref "RP23") (pin "2") (pinfunction "2_2") (pintype "passive"))
      (node (ref "U60") (pin "N5") (pinfunction "A4_N5") (pintype "input"))
    )
    (net (code "8") (name "/QDR2.A5") (class "Default")
      (node (ref "RP23") (pin "3") (pinfunction "3_3") (pintype "passive"))
      (node (ref "U60") (pin "N6") (pinfunction "A5_N6") (pintype "input"))
    )
    (net (code "9") (name "/QDR2.A6") (class "Default")
      (node (ref "RP23") (pin "4") (pinfunction "4_4") (pintype "passive"))
      (node (ref "U60") (pin "N7") (pinfunction "A6_N7") (pintype "input"))
    )
    (net (code "10") (name "/QDR2.A7") (class "Default")
      (node (ref "RP18") (pin "2") (pinfunction "2_2") (pintype "passive"))
      (node (ref "U60") (pin "P4") (pinfunction "A7_P4") (pintype "input"))
    )
    (net (code "11") (name "/QDR2.A8") (class "Default")
      (node (ref "RP18") (pin "4") (pinfunction "4_4") (pintype "passive"))
      (node (ref "U60") (pin "P5") (pinfunction "A8_P5") (pintype "input"))
    )
    (net (code "12") (name "/QDR2.A9") (class "Default")
      (node (ref "RP17") (pin "1") (pinfunction "1_1") (pintype "passive"))
      (node (ref "U60") (pin "P7") (pinfunction "A9_P7") (pintype "input"))
    )
    (net (code "13") (name "/QDR2.A10") (class "Default")
      (node (ref "RP17") (pin "3") (pinfunction "3_3") (pintype "passive"))
      (node (ref "U60") (pin "P8") (pinfunction "A10_P8") (pintype "input"))
    )
    (net (code "14") (name "/QDR2.A11") (class "Default")
      (node (ref "RP24") (pin "2") (pinfunction "2_2") (pintype "passive"))
      (node (ref "U60") (pin "A9") (pinfunction "A11_A9") (pintype "input"))
    )
    (net (code "15") (name "/QDR2.A12") (class "Default")
      (node (ref "RP18") (pin "1") (pinfunction "1_1") (pintype "passive"))
      (node (ref "U60") (pin "R3") (pinfunction "A12_R3") (pintype "input"))
    )
    (net (code "16") (name "/QDR2.A13") (class "Default")
      (node (ref "RP18") (pin "3") (pinfunction "3_3") (pintype "passive"))
      (node (ref "U60") (pin "R4") (pinfunction "A13_R4") (pintype "input"))
    )
    (net (code "17") (name "/QDR2.A14") (class "Default")
      (node (ref "RP23") (pin "1") (pinfunction "1_1") (pintype "passive"))
      (node (ref "U60") (pin "R5") (pinfunction "A14_R5") (pintype "input"))
    )
    (net (code "18") (name "/QDR2.A15") (class "Default")
      (node (ref "R278") (pin "1") (pinfunction "1_1") (pintype "passive"))
      (node (ref "U60") (pin "R7") (pinfunction "A15_R7") (pintype "input"))
    )
    (net (code "19") (name "/QDR2.A16") (class "Default")
      (node (ref "RP17") (pin "2") (pinfunction "2_2") (pintype "passive"))
      (node (ref "U60") (pin "R8") (pinfunction "A16_R8") (pintype "input"))
    )
    (net (code "20") (name "/QDR2.A17") (class "Default")
      (node (ref "RP17") (pin "4") (pinfunction "4_4") (pintype "passive"))
      (node (ref "U60") (pin "R9") (pinfunction "A17_R9") (pintype "input"))
    )
    (net (code "21") (name "/QDR2.A18") (class "Default")
      (node (ref "RP19") (pin "3") (pinfunction "3_3") (pintype "passive"))
      (node (ref "U60") (pin "A3") (pinfunction "A18_A3") (pintype "input"))
    )
    (net (code "22") (name "/QDR2.A19") (class "Default")
      (node (ref "RP24") (pin "1") (pinfunction "1_1") (pintype "passive"))
      (node (ref "U60") (pin "A10") (pinfunction "A19_A10") (pintype "input"))
    )
    (net (code "23") (name "/QDR2.A20") (class "Default")
      (node (ref "RP19") (pin "4") (pinfunction "4_4") (pintype "passive"))
      (node (ref "U60") (pin "A2") (pinfunction "A20_A2") (pintype "input"))
    )
    (net (code "25") (name "/QDR2.BWn0") (class "Default")
      (node (ref "R309") (pin "1") (pinfunction "1_1") (pintype "passive"))
      (node (ref "U60") (pin "B7") (pinfunction "BWS#0_B7") (pintype "input"))
    )
    (net (code "26") (name "/QDR2.BWn1") (class "Default")
      (node (ref "R310") (pin "1") (pinfunction "1_1") (pintype "passive"))
      (node (ref "U60") (pin "A7") (pinfunction "BWS#1_A7") (pintype "input"))
    )
    (net (code "27") (name "/QDR2.BWn2") (class "Default")
      (node (ref "R311") (pin "1") (pinfunction "1_1") (pintype "passive"))
      (node (ref "U60") (pin "A5") (pinfunction "BWS#2_A5") (pintype "input"))
    )
    (net (code "28") (name "/QDR2.BWn3") (class "Default")
      (node (ref "R312") (pin "1") (pinfunction "1_1") (pintype "passive"))
      (node (ref "U60") (pin "B5") (pinfunction "BWS#3_B5") (pintype "input"))
    )
    (net (code "29") (name "/QDR2.D0") (class "Default")
      (node (ref "U60") (pin "P10") (pinfunction "D0_P10") (pintype "input"))
    )
    (net (code "30") (name "/QDR2.D1") (class "Default")
      (node (ref "U60") (pin "N11") (pinfunction "D1_N11") (pintype "input"))
    )
    (net (code "31") (name "/QDR2.D2") (class "Default")
      (node (ref "U60") (pin "M11") (pinfunction "D2_M11") (pintype "input"))
    )
    (net (code "32") (name "/QDR2.D3") (class "Default")
      (node (ref "U60") (pin "K10") (pinfunction "D3_K10") (pintype "input"))
    )
    (net (code "33") (name "/QDR2.D4") (class "Default")
      (node (ref "U60") (pin "J11") (pinfunction "D4_J11") (pintype "input"))
    )
    (net (code "34") (name "/QDR2.D5") (class "Default")
      (node (ref "U60") (pin "G11") (pinfunction "D5_G11") (pintype "input"))
    )
    (net (code "35") (name "/QDR2.D6") (class "Default")
      (node (ref "U60") (pin "E10") (pinfunction "D6_E10") (pintype "input"))
    )
    (net (code "36") (name "/QDR2.D7") (class "Default")
      (node (ref "U60") (pin "D11") (pinfunction "D7_D11") (pintype "input"))
    )
    (net (code "37") (name "/QDR2.D8") (class "Default")
      (node (ref "U60") (pin "C11") (pinfunction "D8_C11") (pintype "input"))
    )
    (net (code "38") (name "/QDR2.D9") (class "Default")
      (node (ref "U60") (pin "N10") (pinfunction "D9_N10") (pintype "input"))
    )
    (net (code "39") (name "/QDR2.D10") (class "Default")
      (node (ref "U60") (pin "M9") (pinfunction "D10_M9") (pintype "input"))
    )
    (net (code "40") (name "/QDR2.D11") (class "Default")
      (node (ref "U60") (pin "L9") (pinfunction "D11_L9") (pintype "input"))
    )
    (net (code "41") (name "/QDR2.D12") (class "Default")
      (node (ref "U60") (pin "J9") (pinfunction "D12_J9") (pintype "input"))
    )
    (net (code "42") (name "/QDR2.D13") (class "Default")
      (node (ref "U60") (pin "G10") (pinfunction "D13_G10") (pintype "input"))
    )
    (net (code "43") (name "/QDR2.D14") (class "Default")
      (node (ref "U60") (pin "F9") (pinfunction "D14_F9") (pintype "input"))
    )
    (net (code "44") (name "/QDR2.D15") (class "Default")
      (node (ref "U60") (pin "D10") (pinfunction "D15_D10") (pintype "input"))
    )
    (net (code "45") (name "/QDR2.D16") (class "Default")
      (node (ref "U60") (pin "C9") (pinfunction "D16_C9") (pintype "input"))
    )
    (net (code "46") (name "/QDR2.D17") (class "Default")
      (node (ref "U60") (pin "B9") (pinfunction "D17_B9") (pintype "input"))
    )
    (net (code "47") (name "/QDR2.D18") (class "Default")
      (node (ref "U60") (pin "B3") (pinfunction "D18_B3") (pintype "input"))
    )
    (net (code "48") (name "/QDR2.D19") (class "Default")
      (node (ref "U60") (pin "C3") (pinfunction "D19_C3") (pintype "input"))
    )
    (net (code "49") (name "/QDR2.D20") (class "Default")
      (node (ref "U60") (pin "D2") (pinfunction "D20_D2") (pintype "input"))
    )
    (net (code "50") (name "/QDR2.D21") (class "Default")
      (node (ref "U60") (pin "F3") (pinfunction "D21_F3") (pintype "input"))
    )
    (net (code "51") (name "/QDR2.D22") (class "Default")
      (node (ref "U60") (pin "G2") (pinfunction "D22_G2") (pintype "input"))
    )
    (net (code "52") (name "/QDR2.D23") (class "Default")
      (node (ref "U60") (pin "J3") (pinfunction "D23_J3") (pintype "input"))
    )
    (net (code "53") (name "/QDR2.D24") (class "Default")
      (node (ref "U60") (pin "L3") (pinfunction "D24_L3") (pintype "input"))
    )
    (net (code "54") (name "/QDR2.D25") (class "Default")
      (node (ref "U60") (pin "M3") (pinfunction "D25_M3") (pintype "input"))
    )
    (net (code "55") (name "/QDR2.D26") (class "Default")
      (node (ref "U60") (pin "N2") (pinfunction "D26_N2") (pintype "input"))
    )
    (net (code "56") (name "/QDR2.D27") (class "Default")
      (node (ref "U60") (pin "C1") (pinfunction "D27_C1") (pintype "input"))
    )
    (net (code "57") (name "/QDR2.D28") (class "Default")
      (node (ref "U60") (pin "D1") (pinfunction "D28_D1") (pintype "input"))
    )
    (net (code "58") (name "/QDR2.D29") (class "Default")
      (node (ref "U60") (pin "E2") (pinfunction "D29_E2") (pintype "input"))
    )
    (net (code "59") (name "/QDR2.D30") (class "Default")
      (node (ref "U60") (pin "G1") (pinfunction "D30_G1") (pintype "input"))
    )
    (net (code "60") (name "/QDR2.D31") (class "Default")
      (node (ref "U60") (pin "J1") (pinfunction "D31_J1") (pintype "input"))
    )
    (net (code "61") (name "/QDR2.D32") (class "Default")
      (node (ref "U60") (pin "K2") (pinfunction "D32_K2") (pintype "input"))
    )
    (net (code "62") (name "/QDR2.D33") (class "Default")
      (node (ref "U60") (pin "M1") (pinfunction "D33_M1") (pintype "input"))
    )
    (net (code "63") (name "/QDR2.D34") (class "Default")
      (node (ref "U60") (pin "N1") (pinfunction "D34_N1") (pintype "input"))
    )
    (net (code "64") (name "/QDR2.D35") (class "Default")
      (node (ref "U60") (pin "P2") (pinfunction "D35_P2") (pintype "input"))
    )
    (net (code "65") (name "/QDR2.DOFFn") (class "Default")
      (node (ref "U60") (pin "H1") (pinfunction "DOFF#_H1") (pintype "input"))
    )
    (net (code "67") (name "/QDR2.K") (class "Default")
      (node (ref "U60") (pin "B6") (pinfunction "K_B6") (pintype "input"))
    )
    (net (code "68") (name "/QDR2.Kn") (class "Default")
      (node (ref "U60") (pin "A6") (pinfunction "K#_A6") (pintype "input"))
    )
    (net (code "69") (name "/QDR2.Q0") (class "Default")
      (node (ref "U60") (pin "P11") (pinfunction "Q0_P11") (pintype "output"))
    )
    (net (code "70") (name "/QDR2.Q1") (class "Default")
      (node (ref "U60") (pin "M10") (pinfunction "Q1_M10") (pintype "output"))
    )
    (net (code "71") (name "/QDR2.Q2") (class "Default")
      (node (ref "U60") (pin "L11") (pinfunction "Q2_L11") (pintype "output"))
    )
    (net (code "72") (name "/QDR2.Q3") (class "Default")
      (node (ref "U60") (pin "K11") (pinfunction "Q3_K11") (pintype "output"))
    )
    (net (code "73") (name "/QDR2.Q4") (class "Default")
      (node (ref "U60") (pin "J10") (pinfunction "Q4_J10") (pintype "output"))
    )
    (net (code "74") (name "/QDR2.Q5") (class "Default")
      (node (ref "U60") (pin "F11") (pinfunction "Q5_F11") (pintype "output"))
    )
    (net (code "75") (name "/QDR2.Q6") (class "Default")
      (node (ref "U60") (pin "E11") (pinfunction "Q6_E11") (pintype "output"))
    )
    (net (code "76") (name "/QDR2.Q7") (class "Default")
      (node (ref "U60") (pin "C10") (pinfunction "Q7_C10") (pintype "output"))
    )
    (net (code "77") (name "/QDR2.Q8") (class "Default")
      (node (ref "U60") (pin "B11") (pinfunction "Q8_B11") (pintype "output"))
    )
    (net (code "78") (name "/QDR2.Q9") (class "Default")
      (node (ref "U60") (pin "P9") (pinfunction "Q9_P9") (pintype "output"))
    )
    (net (code "79") (name "/QDR2.Q10") (class "Default")
      (node (ref "U60") (pin "N9") (pinfunction "Q10_N9") (pintype "output"))
    )
    (net (code "80") (name "/QDR2.Q11") (class "Default")
      (node (ref "U60") (pin "L10") (pinfunction "Q11_L10") (pintype "output"))
    )
    (net (code "81") (name "/QDR2.Q12") (class "Default")
      (node (ref "U60") (pin "K9") (pinfunction "Q12_K9") (pintype "output"))
    )
    (net (code "82") (name "/QDR2.Q13") (class "Default")
      (node (ref "U60") (pin "G9") (pinfunction "Q13_G9") (pintype "output"))
    )
    (net (code "83") (name "/QDR2.Q14") (class "Default")
      (node (ref "U60") (pin "F10") (pinfunction "Q14_F10") (pintype "output"))
    )
    (net (code "84") (name "/QDR2.Q15") (class "Default")
      (node (ref "U60") (pin "E9") (pinfunction "Q15_E9") (pintype "output"))
    )
    (net (code "85") (name "/QDR2.Q16") (class "Default")
      (node (ref "U60") (pin "D9") (pinfunction "Q16_D9") (pintype "output"))
    )
    (net (code "86") (name "/QDR2.Q17") (class "Default")
      (node (ref "U60") (pin "B10") (pinfunction "Q17_B10") (pintype "output"))
    )
    (net (code "87") (name "/QDR2.Q18") (class "Default")
      (node (ref "U60") (pin "B2") (pinfunction "Q18_B2") (pintype "output"))
    )
    (net (code "88") (name "/QDR2.Q19") (class "Default")
      (node (ref "U60") (pin "D3") (pinfunction "Q19_D3") (pintype "output"))
    )
    (net (code "89") (name "/QDR2.Q20") (class "Default")
      (node (ref "U60") (pin "E3") (pinfunction "Q20_E3") (pintype "output"))
    )
    (net (code "90") (name "/QDR2.Q21") (class "Default")
      (node (ref "U60") (pin "F2") (pinfunction "Q21_F2") (pintype "output"))
    )
    (net (code "91") (name "/QDR2.Q22") (class "Default")
      (node (ref "U60") (pin "G3") (pinfunction "Q22_G3") (pintype "output"))
    )
    (net (code "92") (name "/QDR2.Q23") (class "Default")
      (node (ref "U60") (pin "K3") (pinfunction "Q23_K3") (pintype "output"))
    )
    (net (code "93") (name "/QDR2.Q24") (class "Default")
      (node (ref "U60") (pin "L2") (pinfunction "Q24_L2") (pintype "output"))
    )
    (net (code "94") (name "/QDR2.Q25") (class "Default")
      (node (ref "U60") (pin "N3") (pinfunction "Q25_N3") (pintype "output"))
    )
    (net (code "95") (name "/QDR2.Q26") (class "Default")
      (node (ref "U60") (pin "P3") (pinfunction "Q26_P3") (pintype "output"))
    )
    (net (code "96") (name "/QDR2.Q27") (class "Default")
      (node (ref "U60") (pin "B1") (pinfunction "Q27_B1") (pintype "output"))
    )
    (net (code "97") (name "/QDR2.Q28") (class "Default")
      (node (ref "U60") (pin "C2") (pinfunction "Q28_C2") (pintype "output"))
    )
    (net (code "98") (name "/QDR2.Q29") (class "Default")
      (node (ref "U60") (pin "E1") (pinfunction "Q29_E1") (pintype "output"))
    )
    (net (code "99") (name "/QDR2.Q30") (class "Default")
      (node (ref "U60") (pin "F1") (pinfunction "Q30_F1") (pintype "output"))
    )
    (net (code "100") (name "/QDR2.Q31") (class "Default")
      (node (ref "U60") (pin "J2") (pinfunction "Q31_J2") (pintype "output"))
    )
    (net (code "101") (name "/QDR2.Q32") (class "Default")
      (node (ref "U60") (pin "K1") (pinfunction "Q32_K1") (pintype "output"))
    )
    (net (code "102") (name "/QDR2.Q33") (class "Default")
      (node (ref "U60") (pin "L1") (pinfunction "Q33_L1") (pintype "output"))
    )
    (net (code "103") (name "/QDR2.Q34") (class "Default")
      (node (ref "U60") (pin "M2") (pinfunction "Q34_M2") (pintype "output"))
    )
    (net (code "104") (name "/QDR2.Q35") (class "Default")
      (node (ref "U60") (pin "P1") (pinfunction "Q35_P1") (pintype "output"))
    )
    (net (code "106") (name "/QDR2.RDn") (class "Default")
      (node (ref "RP24") (pin "4") (pinfunction "4_4") (pintype "passive"))
      (node (ref "U60") (pin "A8") (pinfunction "RPS#_A8") (pintype "input"))
    )
    (net (code "107") (name "/QDR2.WRn") (class "Default")
      (node (ref "RP19") (pin "2") (pinfunction "2_2") (pintype "passive"))
      (node (ref "U60") (pin "A4") (pinfunction "WPS#_A4") (pintype "input"))
    )
    (net (code "108") (name "/QDR2_TCK") (class "Default")
      (node (ref "U60") (pin "R2") (pinfunction "TCK_R2") (pintype "input"))
    )
    (net (code "109") (name "/QDR2_TDI") (class "Default")
      (node (ref "U60") (pin "R11") (pinfunction "TDI_R11") (pintype "input"))
    )
    (net (code "110") (name "/QDR2_TDO") (class "Default")
      (node (ref "U60") (pin "R1") (pinfunction "TDO_R1") (pintype "output"))
    )
    (net (code "111") (name "/QDR2_TMS") (class "Default")
      (node (ref "U60") (pin "R10") (pinfunction "TMS_R10") (pintype "input"))
    )
    (net (code "112") (name "/QDR3.A0") (class "Default")
      (node (ref "RP22") (pin "1") (pinfunction "1_1") (pintype "passive"))
      (node (ref "U61") (pin "B4") (pinfunction "A0_B4") (pintype "input"))
    )
    (net (code "113") (name "/QDR3.A1") (class "Default")
      (node (ref "RP26") (pin "3") (pinfunction "3_3") (pintype "passive"))
      (node (ref "U61") (pin "B8") (pinfunction "A1_B8") (pintype "input"))
    )
    (net (code "114") (name "/QDR3.A2") (class "Default")
      (node (ref "R283") (pin "1") (pinfunction "1_1") (pintype "passive"))
      (node (ref "U61") (pin "C5") (pinfunction "A2_C5") (pintype "input"))
    )
    (net (code "115") (name "/QDR3.A3") (class "Default")
      (node (ref "R281") (pin "1") (pinfunction "1_1") (pintype "passive"))
      (node (ref "U61") (pin "C7") (pinfunction "A3_C7") (pintype "input"))
    )
    (net (code "116") (name "/QDR3.A4") (class "Default")
      (node (ref "RP25") (pin "2") (pinfunction "2_2") (pintype "passive"))
      (node (ref "U61") (pin "N5") (pinfunction "A4_N5") (pintype "input"))
    )
    (net (code "117") (name "/QDR3.A5") (class "Default")
      (node (ref "RP25") (pin "3") (pinfunction "3_3") (pintype "passive"))
      (node (ref "U61") (pin "N6") (pinfunction "A5_N6") (pintype "input"))
    )
    (net (code "118") (name "/QDR3.A6") (class "Default")
      (node (ref "RP25") (pin "4") (pinfunction "4_4") (pintype "passive"))
      (node (ref "U61") (pin "N7") (pinfunction "A6_N7") (pintype "input"))
    )
    (net (code "119") (name "/QDR3.A7") (class "Default")
      (node (ref "RP21") (pin "2") (pinfunction "2_2") (pintype "passive"))
      (node (ref "U61") (pin "P4") (pinfunction "A7_P4") (pintype "input"))
    )
    (net (code "120") (name "/QDR3.A8") (class "Default")
      (node (ref "RP21") (pin "4") (pinfunction "4_4") (pintype "passive"))
      (node (ref "U61") (pin "P5") (pinfunction "A8_P5") (pintype "input"))
    )
    (net (code "121") (name "/QDR3.A9") (class "Default")
      (node (ref "RP20") (pin "1") (pinfunction "1_1") (pintype "passive"))
      (node (ref "U61") (pin "P7") (pinfunction "A9_P7") (pintype "input"))
    )
    (net (code "122") (name "/QDR3.A10") (class "Default")
      (node (ref "RP20") (pin "3") (pinfunction "3_3") (pintype "passive"))
      (node (ref "U61") (pin "P8") (pinfunction "A10_P8") (pintype "input"))
    )
    (net (code "123") (name "/QDR3.A11") (class "Default")
      (node (ref "RP26") (pin "2") (pinfunction "2_2") (pintype "passive"))
      (node (ref "U61") (pin "A9") (pinfunction "A11_A9") (pintype "input"))
    )
    (net (code "124") (name "/QDR3.A12") (class "Default")
      (node (ref "RP21") (pin "1") (pinfunction "1_1") (pintype "passive"))
      (node (ref "U61") (pin "R3") (pinfunction "A12_R3") (pintype "input"))
    )
    (net (code "125") (name "/QDR3.A13") (class "Default")
      (node (ref "RP21") (pin "3") (pinfunction "3_3") (pintype "passive"))
      (node (ref "U61") (pin "R4") (pinfunction "A13_R4") (pintype "input"))
    )
    (net (code "126") (name "/QDR3.A14") (class "Default")
      (node (ref "RP25") (pin "1") (pinfunction "1_1") (pintype "passive"))
      (node (ref "U61") (pin "R5") (pinfunction "A14_R5") (pintype "input"))
    )
    (net (code "127") (name "/QDR3.A15") (class "Default")
      (node (ref "R279") (pin "1") (pinfunction "1_1") (pintype "passive"))
      (node (ref "U61") (pin "R7") (pinfunction "A15_R7") (pintype "input"))
    )
    (net (code "128") (name "/QDR3.A16") (class "Default")
      (node (ref "RP20") (pin "2") (pinfunction "2_2") (pintype "passive"))
      (node (ref "U61") (pin "R8") (pinfunction "A16_R8") (pintype "input"))
    )
    (net (code "129") (name "/QDR3.A17") (class "Default")
      (node (ref "RP20") (pin "4") (pinfunction "4_4") (pintype "passive"))
      (node (ref "U61") (pin "R9") (pinfunction "A17_R9") (pintype "input"))
    )
    (net (code "130") (name "/QDR3.A18") (class "Default")
      (node (ref "RP22") (pin "3") (pinfunction "3_3") (pintype "passive"))
      (node (ref "U61") (pin "A3") (pinfunction "A18_A3") (pintype "input"))
    )
    (net (code "131") (name "/QDR3.A19") (class "Default")
      (node (ref "RP26") (pin "1") (pinfunction "1_1") (pintype "passive"))
      (node (ref "U61") (pin "A10") (pinfunction "A19_A10") (pintype "input"))
    )
    (net (code "132") (name "/QDR3.A20") (class "Default")
      (node (ref "RP22") (pin "4") (pinfunction "4_4") (pintype "passive"))
      (node (ref "U61") (pin "A2") (pinfunction "A20_A2") (pintype "input"))
    )
    (net (code "134") (name "/QDR3.BWn0") (class "Default")
      (node (ref "R313") (pin "1") (pinfunction "1_1") (pintype "passive"))
      (node (ref "U61") (pin "B7") (pinfunction "BWS#0_B7") (pintype "input"))
    )
    (net (code "135") (name "/QDR3.BWn1") (class "Default")
      (node (ref "R314") (pin "1") (pinfunction "1_1") (pintype "passive"))
      (node (ref "U61") (pin "A7") (pinfunction "BWS#1_A7") (pintype "input"))
    )
    (net (code "136") (name "/QDR3.BWn2") (class "Default")
      (node (ref "R315") (pin "1") (pinfunction "1_1") (pintype "passive"))
      (node (ref "U61") (pin "A5") (pinfunction "BWS#2_A5") (pintype "input"))
    )
    (net (code "137") (name "/QDR3.BWn3") (class "Default")
      (node (ref "R316") (pin "1") (pinfunction "1_1") (pintype "passive"))
      (node (ref "U61") (pin "B5") (pinfunction "BWS#3_B5") (pintype "input"))
    )
    (net (code "138") (name "/QDR3.D0") (class "Default")
      (node (ref "U61") (pin "P10") (pinfunction "D0_P10") (pintype "input"))
    )
    (net (code "139") (name "/QDR3.D1") (class "Default")
      (node (ref "U61") (pin "N11") (pinfunction "D1_N11") (pintype "input"))
    )
    (net (code "140") (name "/QDR3.D2") (class "Default")
      (node (ref "U61") (pin "M11") (pinfunction "D2_M11") (pintype "input"))
    )
    (net (code "141") (name "/QDR3.D3") (class "Default")
      (node (ref "U61") (pin "K10") (pinfunction "D3_K10") (pintype "input"))
    )
    (net (code "142") (name "/QDR3.D4") (class "Default")
      (node (ref "U61") (pin "J11") (pinfunction "D4_J11") (pintype "input"))
    )
    (net (code "143") (name "/QDR3.D5") (class "Default")
      (node (ref "U61") (pin "G11") (pinfunction "D5_G11") (pintype "input"))
    )
    (net (code "144") (name "/QDR3.D6") (class "Default")
      (node (ref "U61") (pin "E10") (pinfunction "D6_E10") (pintype "input"))
    )
    (net (code "145") (name "/QDR3.D7") (class "Default")
      (node (ref "U61") (pin "D11") (pinfunction "D7_D11") (pintype "input"))
    )
    (net (code "146") (name "/QDR3.D8") (class "Default")
      (node (ref "U61") (pin "C11") (pinfunction "D8_C11") (pintype "input"))
    )
    (net (code "147") (name "/QDR3.D9") (class "Default")
      (node (ref "U61") (pin "N10") (pinfunction "D9_N10") (pintype "input"))
    )
    (net (code "148") (name "/QDR3.D10") (class "Default")
      (node (ref "U61") (pin "M9") (pinfunction "D10_M9") (pintype "input"))
    )
    (net (code "149") (name "/QDR3.D11") (class "Default")
      (node (ref "U61") (pin "L9") (pinfunction "D11_L9") (pintype "input"))
    )
    (net (code "150") (name "/QDR3.D12") (class "Default")
      (node (ref "U61") (pin "J9") (pinfunction "D12_J9") (pintype "input"))
    )
    (net (code "151") (name "/QDR3.D13") (class "Default")
      (node (ref "U61") (pin "G10") (pinfunction "D13_G10") (pintype "input"))
    )
    (net (code "152") (name "/QDR3.D14") (class "Default")
      (node (ref "U61") (pin "F9") (pinfunction "D14_F9") (pintype "input"))
    )
    (net (code "153") (name "/QDR3.D15") (class "Default")
      (node (ref "U61") (pin "D10") (pinfunction "D15_D10") (pintype "input"))
    )
    (net (code "154") (name "/QDR3.D16") (class "Default")
      (node (ref "U61") (pin "C9") (pinfunction "D16_C9") (pintype "input"))
    )
    (net (code "155") (name "/QDR3.D17") (class "Default")
      (node (ref "U61") (pin "B9") (pinfunction "D17_B9") (pintype "input"))
    )
    (net (code "156") (name "/QDR3.D18") (class "Default")
      (node (ref "U61") (pin "B3") (pinfunction "D18_B3") (pintype "input"))
    )
    (net (code "157") (name "/QDR3.D19") (class "Default")
      (node (ref "U61") (pin "C3") (pinfunction "D19_C3") (pintype "input"))
    )
    (net (code "158") (name "/QDR3.D20") (class "Default")
      (node (ref "U61") (pin "D2") (pinfunction "D20_D2") (pintype "input"))
    )
    (net (code "159") (name "/QDR3.D21") (class "Default")
      (node (ref "U61") (pin "F3") (pinfunction "D21_F3") (pintype "input"))
    )
    (net (code "160") (name "/QDR3.D22") (class "Default")
      (node (ref "U61") (pin "G2") (pinfunction "D22_G2") (pintype "input"))
    )
    (net (code "161") (name "/QDR3.D23") (class "Default")
      (node (ref "U61") (pin "J3") (pinfunction "D23_J3") (pintype "input"))
    )
    (net (code "162") (name "/QDR3.D24") (class "Default")
      (node (ref "U61") (pin "L3") (pinfunction "D24_L3") (pintype "input"))
    )
    (net (code "163") (name "/QDR3.D25") (class "Default")
      (node (ref "U61") (pin "M3") (pinfunction "D25_M3") (pintype "input"))
    )
    (net (code "164") (name "/QDR3.D26") (class "Default")
      (node (ref "U61") (pin "N2") (pinfunction "D26_N2") (pintype "input"))
    )
    (net (code "165") (name "/QDR3.D27") (class "Default")
      (node (ref "U61") (pin "C1") (pinfunction "D27_C1") (pintype "input"))
    )
    (net (code "166") (name "/QDR3.D28") (class "Default")
      (node (ref "U61") (pin "D1") (pinfunction "D28_D1") (pintype "input"))
    )
    (net (code "167") (name "/QDR3.D29") (class "Default")
      (node (ref "U61") (pin "E2") (pinfunction "D29_E2") (pintype "input"))
    )
    (net (code "168") (name "/QDR3.D30") (class "Default")
      (node (ref "U61") (pin "G1") (pinfunction "D30_G1") (pintype "input"))
    )
    (net (code "169") (name "/QDR3.D31") (class "Default")
      (node (ref "U61") (pin "J1") (pinfunction "D31_J1") (pintype "input"))
    )
    (net (code "170") (name "/QDR3.D32") (class "Default")
      (node (ref "U61") (pin "K2") (pinfunction "D32_K2") (pintype "input"))
    )
    (net (code "171") (name "/QDR3.D33") (class "Default")
      (node (ref "U61") (pin "M1") (pinfunction "D33_M1") (pintype "input"))
    )
    (net (code "172") (name "/QDR3.D34") (class "Default")
      (node (ref "U61") (pin "N1") (pinfunction "D34_N1") (pintype "input"))
    )
    (net (code "173") (name "/QDR3.D35") (class "Default")
      (node (ref "U61") (pin "P2") (pinfunction "D35_P2") (pintype "input"))
    )
    (net (code "174") (name "/QDR3.DOFFn") (class "Default")
      (node (ref "U61") (pin "H1") (pinfunction "DOFF#_H1") (pintype "input"))
    )
    (net (code "176") (name "/QDR3.K") (class "Default")
      (node (ref "U61") (pin "B6") (pinfunction "K_B6") (pintype "input"))
    )
    (net (code "177") (name "/QDR3.Kn") (class "Default")
      (node (ref "U61") (pin "A6") (pinfunction "K#_A6") (pintype "input"))
    )
    (net (code "178") (name "/QDR3.Q0") (class "Default")
      (node (ref "U61") (pin "P11") (pinfunction "Q0_P11") (pintype "output"))
    )
    (net (code "179") (name "/QDR3.Q1") (class "Default")
      (node (ref "U61") (pin "M10") (pinfunction "Q1_M10") (pintype "output"))
    )
    (net (code "180") (name "/QDR3.Q2") (class "Default")
      (node (ref "U61") (pin "L11") (pinfunction "Q2_L11") (pintype "output"))
    )
    (net (code "181") (name "/QDR3.Q3") (class "Default")
      (node (ref "U61") (pin "K11") (pinfunction "Q3_K11") (pintype "output"))
    )
    (net (code "182") (name "/QDR3.Q4") (class "Default")
      (node (ref "U61") (pin "J10") (pinfunction "Q4_J10") (pintype "output"))
    )
    (net (code "183") (name "/QDR3.Q5") (class "Default")
      (node (ref "U61") (pin "F11") (pinfunction "Q5_F11") (pintype "output"))
    )
    (net (code "184") (name "/QDR3.Q6") (class "Default")
      (node (ref "U61") (pin "E11") (pinfunction "Q6_E11") (pintype "output"))
    )
    (net (code "185") (name "/QDR3.Q7") (class "Default")
      (node (ref "U61") (pin "C10") (pinfunction "Q7_C10") (pintype "output"))
    )
    (net (code "186") (name "/QDR3.Q8") (class "Default")
      (node (ref "U61") (pin "B11") (pinfunction "Q8_B11") (pintype "output"))
    )
    (net (code "187") (name "/QDR3.Q9") (class "Default")
      (node (ref "U61") (pin "P9") (pinfunction "Q9_P9") (pintype "output"))
    )
    (net (code "188") (name "/QDR3.Q10") (class "Default")
      (node (ref "U61") (pin "N9") (pinfunction "Q10_N9") (pintype "output"))
    )
    (net (code "189") (name "/QDR3.Q11") (class "Default")
      (node (ref "U61") (pin "L10") (pinfunction "Q11_L10") (pintype "output"))
    )
    (net (code "190") (name "/QDR3.Q12") (class "Default")
      (node (ref "U61") (pin "K9") (pinfunction "Q12_K9") (pintype "output"))
    )
    (net (code "191") (name "/QDR3.Q13") (class "Default")
      (node (ref "U61") (pin "G9") (pinfunction "Q13_G9") (pintype "output"))
    )
    (net (code "192") (name "/QDR3.Q14") (class "Default")
      (node (ref "U61") (pin "F10") (pinfunction "Q14_F10") (pintype "output"))
    )
    (net (code "193") (name "/QDR3.Q15") (class "Default")
      (node (ref "U61") (pin "E9") (pinfunction "Q15_E9") (pintype "output"))
    )
    (net (code "194") (name "/QDR3.Q16") (class "Default")
      (node (ref "U61") (pin "D9") (pinfunction "Q16_D9") (pintype "output"))
    )
    (net (code "195") (name "/QDR3.Q17") (class "Default")
      (node (ref "U61") (pin "B10") (pinfunction "Q17_B10") (pintype "output"))
    )
    (net (code "196") (name "/QDR3.Q18") (class "Default")
      (node (ref "U61") (pin "B2") (pinfunction "Q18_B2") (pintype "output"))
    )
    (net (code "197") (name "/QDR3.Q19") (class "Default")
      (node (ref "U61") (pin "D3") (pinfunction "Q19_D3") (pintype "output"))
    )
    (net (code "198") (name "/QDR3.Q20") (class "Default")
      (node (ref "U61") (pin "E3") (pinfunction "Q20_E3") (pintype "output"))
    )
    (net (code "199") (name "/QDR3.Q21") (class "Default")
      (node (ref "U61") (pin "F2") (pinfunction "Q21_F2") (pintype "output"))
    )
    (net (code "200") (name "/QDR3.Q22") (class "Default")
      (node (ref "U61") (pin "G3") (pinfunction "Q22_G3") (pintype "output"))
    )
    (net (code "201") (name "/QDR3.Q23") (class "Default")
      (node (ref "U61") (pin "K3") (pinfunction "Q23_K3") (pintype "output"))
    )
    (net (code "202") (name "/QDR3.Q24") (class "Default")
      (node (ref "U61") (pin "L2") (pinfunction "Q24_L2") (pintype "output"))
    )
    (net (code "203") (name "/QDR3.Q25") (class "Default")
      (node (ref "U61") (pin "N3") (pinfunction "Q25_N3") (pintype "output"))
    )
    (net (code "204") (name "/QDR3.Q26") (class "Default")
      (node (ref "U61") (pin "P3") (pinfunction "Q26_P3") (pintype "output"))
    )
    (net (code "205") (name "/QDR3.Q27") (class "Default")
      (node (ref "U61") (pin "B1") (pinfunction "Q27_B1") (pintype "output"))
    )
    (net (code "206") (name "/QDR3.Q28") (class "Default")
      (node (ref "U61") (pin "C2") (pinfunction "Q28_C2") (pintype "output"))
    )
    (net (code "207") (name "/QDR3.Q29") (class "Default")
      (node (ref "U61") (pin "E1") (pinfunction "Q29_E1") (pintype "output"))
    )
    (net (code "208") (name "/QDR3.Q30") (class "Default")
      (node (ref "U61") (pin "F1") (pinfunction "Q30_F1") (pintype "output"))
    )
    (net (code "209") (name "/QDR3.Q31") (class "Default")
      (node (ref "U61") (pin "J2") (pinfunction "Q31_J2") (pintype "output"))
    )
    (net (code "210") (name "/QDR3.Q32") (class "Default")
      (node (ref "U61") (pin "K1") (pinfunction "Q32_K1") (pintype "output"))
    )
    (net (code "211") (name "/QDR3.Q33") (class "Default")
      (node (ref "U61") (pin "L1") (pinfunction "Q33_L1") (pintype "output"))
    )
    (net (code "212") (name "/QDR3.Q34") (class "Default")
      (node (ref "U61") (pin "M2") (pinfunction "Q34_M2") (pintype "output"))
    )
    (net (code "213") (name "/QDR3.Q35") (class "Default")
      (node (ref "U61") (pin "P1") (pinfunction "Q35_P1") (pintype "output"))
    )
    (net (code "215") (name "/QDR3.RDn") (class "Default")
      (node (ref "RP26") (pin "4") (pinfunction "4_4") (pintype "passive"))
      (node (ref "U61") (pin "A8") (pinfunction "RPS#_A8") (pintype "input"))
    )
    (net (code "216") (name "/QDR3.WRn") (class "Default")
      (node (ref "RP22") (pin "2") (pinfunction "2_2") (pintype "passive"))
      (node (ref "U61") (pin "A4") (pinfunction "WPS#_A4") (pintype "input"))
    )
    (net (code "217") (name "/QDR3_TCK") (class "Default")
      (node (ref "U61") (pin "R2") (pinfunction "TCK_R2") (pintype "input"))
    )
    (net (code "218") (name "/QDR3_TDI") (class "Default")
      (node (ref "U61") (pin "R11") (pinfunction "TDI_R11") (pintype "input"))
    )
    (net (code "219") (name "/QDR3_TDO") (class "Default")
      (node (ref "U61") (pin "R1") (pinfunction "TDO_R1") (pintype "output"))
    )
    (net (code "220") (name "/QDR3_TMS") (class "Default")
      (node (ref "U61") (pin "R10") (pinfunction "TMS_R10") (pintype "input"))
    )
    (net (code "224") (name "1V5") (class "Default")
      (node (ref "C572") (pin "2") (pinfunction "2_2") (pintype "passive"))
      (node (ref "C573") (pin "2") (pinfunction "2_2") (pintype "passive"))
      (node (ref "C574") (pin "2") (pinfunction "2_2") (pintype "passive"))
      (node (ref "C575") (pin "2") (pinfunction "2_2") (pintype "passive"))
      (node (ref "C576") (pin "2") (pinfunction "2_2") (pintype "passive"))
      (node (ref "C577") (pin "2") (pinfunction "2_2") (pintype "passive"))
      (node (ref "C578") (pin "2") (pinfunction "2_2") (pintype "passive"))
      (node (ref "C579") (pin "2") (pinfunction "2_2") (pintype "passive"))
      (node (ref "C580") (pin "2") (pinfunction "2_2") (pintype "passive"))
      (node (ref "C582") (pin "2") (pinfunction "2_2") (pintype "passive"))
      (node (ref "C583") (pin "2") (pinfunction "2_2") (pintype "passive"))
      (node (ref "C584") (pin "2") (pinfunction "2_2") (pintype "passive"))
      (node (ref "C585") (pin "2") (pinfunction "2_2") (pintype "passive"))
      (node (ref "C586") (pin "2") (pinfunction "2_2") (pintype "passive"))
      (node (ref "C587") (pin "2") (pinfunction "2_2") (pintype "passive"))
      (node (ref "C588") (pin "2") (pinfunction "2_2") (pintype "passive"))
      (node (ref "C589") (pin "2") (pinfunction "2_2") (pintype "passive"))
      (node (ref "C590") (pin "2") (pinfunction "2_2") (pintype "passive"))
      (node (ref "C627") (pin "2") (pinfunction "2_2") (pintype "passive"))
      (node (ref "R364") (pin "2") (pinfunction "2_2") (pintype "passive"))
      (node (ref "R365") (pin "2") (pinfunction "2_2") (pintype "passive"))
      (node (ref "R397") (pin "2") (pinfunction "2_2") (pintype "passive"))
      (node (ref "R398") (pin "2") (pinfunction "2_2") (pintype "passive"))
      (node (ref "R399") (pin "2") (pinfunction "2_2") (pintype "passive"))
      (node (ref "R401") (pin "2") (pinfunction "2_2") (pintype "passive"))
      (node (ref "R411") (pin "2") (pinfunction "2_2") (pintype "passive"))
      (node (ref "R417") (pin "2") (pinfunction "2_2") (pintype "passive"))
      (node (ref "U60") (pin "E4") (pinfunction "VDDQ0_E4") (pintype "power_in"))
      (node (ref "U60") (pin "E8") (pinfunction "VDDQ1_E8") (pintype "power_in"))
      (node (ref "U60") (pin "F4") (pinfunction "VDDQ2_F4") (pintype "power_in"))
      (node (ref "U60") (pin "F8") (pinfunction "VDDQ3_F8") (pintype "power_in"))
      (node (ref "U60") (pin "G4") (pinfunction "VDDQ4_G4") (pintype "power_in"))
      (node (ref "U60") (pin "G8") (pinfunction "VDDQ5_G8") (pintype "power_in"))
      (node (ref "U60") (pin "H3") (pinfunction "VDDQ6_H3") (pintype "power_in"))
      (node (ref "U60") (pin "H4") (pinfunction "VDDQ7_H4") (pintype "power_in"))
      (node (ref "U60") (pin "H8") (pinfunction "VDDQ8_H8") (pintype "power_in"))
      (node (ref "U60") (pin "H9") (pinfunction "VDDQ9_H9") (pintype "power_in"))
      (node (ref "U60") (pin "J4") (pinfunction "VDDQ10_J4") (pintype "power_in"))
      (node (ref "U60") (pin "J8") (pinfunction "VDDQ11_J8") (pintype "power_in"))
      (node (ref "U60") (pin "K4") (pinfunction "VDDQ12_K4") (pintype "power_in"))
      (node (ref "U60") (pin "K8") (pinfunction "VDDQ13_K8") (pintype "power_in"))
      (node (ref "U60") (pin "L4") (pinfunction "VDDQ14_L4") (pintype "power_in"))
      (node (ref "U60") (pin "L8") (pinfunction "VDDQ15_L8") (pintype "power_in"))
      (node (ref "U61") (pin "E4") (pinfunction "VDDQ0_E4") (pintype "power_in"))
      (node (ref "U61") (pin "E8") (pinfunction "VDDQ1_E8") (pintype "power_in"))
      (node (ref "U61") (pin "F4") (pinfunction "VDDQ2_F4") (pintype "power_in"))
      (node (ref "U61") (pin "F8") (pinfunction "VDDQ3_F8") (pintype "power_in"))
      (node (ref "U61") (pin "G4") (pinfunction "VDDQ4_G4") (pintype "power_in"))
      (node (ref "U61") (pin "G8") (pinfunction "VDDQ5_G8") (pintype "power_in"))
      (node (ref "U61") (pin "H3") (pinfunction "VDDQ6_H3") (pintype "power_in"))
      (node (ref "U61") (pin "H4") (pinfunction "VDDQ7_H4") (pintype "power_in"))
      (node (ref "U61") (pin "H8") (pinfunction "VDDQ8_H8") (pintype "power_in"))
      (node (ref "U61") (pin "H9") (pinfunction "VDDQ9_H9") (pintype "power_in"))
      (node (ref "U61") (pin "J4") (pinfunction "VDDQ10_J4") (pintype "power_in"))
      (node (ref "U61") (pin "J8") (pinfunction "VDDQ11_J8") (pintype "power_in"))
      (node (ref "U61") (pin "K4") (pinfunction "VDDQ12_K4") (pintype "power_in"))
      (node (ref "U61") (pin "K8") (pinfunction "VDDQ13_K8") (pintype "power_in"))
      (node (ref "U61") (pin "L4") (pinfunction "VDDQ14_L4") (pintype "power_in"))
      (node (ref "U61") (pin "L8") (pinfunction "VDDQ15_L8") (pintype "power_in"))
      (node (ref "U62") (pin "1") (pinfunction "VDDQSNS_1") (pintype "input"))
      (node (ref "U62") (pin "2") (pinfunction "VLDOIN_2") (pintype "input"))
    )
    (net (code "225") (name "1V8") (class "Default")
      (node (ref "C592") (pin "2") (pinfunction "2_2") (pintype "passive"))
      (node (ref "C593") (pin "2") (pinfunction "2_2") (pintype "passive"))
      (node (ref "C594") (pin "2") (pinfunction "2_2") (pintype "passive"))
      (node (ref "C595") (pin "2") (pinfunction "2_2") (pintype "passive"))
      (node (ref "C596") (pin "2") (pinfunction "2_2") (pintype "passive"))
      (node (ref "C597") (pin "2") (pinfunction "2_2") (pintype "passive"))
      (node (ref "C598") (pin "2") (pinfunction "2_2") (pintype "passive"))
      (node (ref "C599") (pin "2") (pinfunction "2_2") (pintype "passive"))
      (node (ref "C600") (pin "2") (pinfunction "2_2") (pintype "passive"))
      (node (ref "C602") (pin "2") (pinfunction "2_2") (pintype "passive"))
      (node (ref "C603") (pin "2") (pinfunction "2_2") (pintype "passive"))
      (node (ref "C604") (pin "2") (pinfunction "2_2") (pintype "passive"))
      (node (ref "C605") (pin "2") (pinfunction "2_2") (pintype "passive"))
      (node (ref "C606") (pin "2") (pinfunction "2_2") (pintype "passive"))
      (node (ref "C607") (pin "2") (pinfunction "2_2") (pintype "passive"))
      (node (ref "C608") (pin "2") (pinfunction "2_2") (pintype "passive"))
      (node (ref "C609") (pin "2") (pinfunction "2_2") (pintype "passive"))
      (node (ref "C610") (pin "2") (pinfunction "2_2") (pintype "passive"))
      (node (ref "U60") (pin "F5") (pinfunction "VDD0_F5") (pintype "power_in"))
      (node (ref "U60") (pin "F7") (pinfunction "VDD1_F7") (pintype "power_in"))
      (node (ref "U60") (pin "G5") (pinfunction "VDD2_G5") (pintype "power_in"))
      (node (ref "U60") (pin "G7") (pinfunction "VDD3_G7") (pintype "power_in"))
      (node (ref "U60") (pin "H5") (pinfunction "VDD4_H5") (pintype "power_in"))
      (node (ref "U60") (pin "H7") (pinfunction "VDD5_H7") (pintype "power_in"))
      (node (ref "U60") (pin "J5") (pinfunction "VDD6_J5") (pintype "power_in"))
      (node (ref "U60") (pin "J7") (pinfunction "VDD7_J7") (pintype "power_in"))
      (node (ref "U60") (pin "K5") (pinfunction "VDD8_K5") (pintype "power_in"))
      (node (ref "U60") (pin "K7") (pinfunction "VDD9_K7") (pintype "power_in"))
      (node (ref "U61") (pin "F5") (pinfunction "VDD0_F5") (pintype "power_in"))
      (node (ref "U61") (pin "F7") (pinfunction "VDD1_F7") (pintype "power_in"))
      (node (ref "U61") (pin "G5") (pinfunction "VDD2_G5") (pintype "power_in"))
      (node (ref "U61") (pin "G7") (pinfunction "VDD3_G7") (pintype "power_in"))
      (node (ref "U61") (pin "H5") (pinfunction "VDD4_H5") (pintype "power_in"))
      (node (ref "U61") (pin "H7") (pinfunction "VDD5_H7") (pintype "power_in"))
      (node (ref "U61") (pin "J5") (pinfunction "VDD6_J5") (pintype "power_in"))
      (node (ref "U61") (pin "J7") (pinfunction "VDD7_J7") (pintype "power_in"))
      (node (ref "U61") (pin "K5") (pinfunction "VDD8_K5") (pintype "power_in"))
      (node (ref "U61") (pin "K7") (pinfunction "VDD9_K7") (pintype "power_in"))
    )
    (net (code "226") (name "5V") (class "Default")
      (node (ref "C626") (pin "2") (pinfunction "2_2") (pintype "passive"))
      (node (ref "R374") (pin "1") (pinfunction "1_1") (pintype "passive"))
      (node (ref "R375") (pin "1") (pinfunction "1_1") (pintype "passive"))
      (node (ref "U62") (pin "10") (pinfunction "VIN_10") (pintype "input"))
    )
    (net (code "227") (name "GND") (class "Default")
      (node (ref "C572") (pin "1") (pinfunction "1_1") (pintype "passive"))
      (node (ref "C573") (pin "1") (pinfunction "1_1") (pintype "passive"))
      (node (ref "C574") (pin "1") (pinfunction "1_1") (pintype "passive"))
      (node (ref "C575") (pin "1") (pinfunction "1_1") (pintype "passive"))
      (node (ref "C576") (pin "1") (pinfunction "1_1") (pintype "passive"))
      (node (ref "C577") (pin "1") (pinfunction "1_1") (pintype "passive"))
      (node (ref "C578") (pin "1") (pinfunction "1_1") (pintype "passive"))
      (node (ref "C579") (pin "1") (pinfunction "1_1") (pintype "passive"))
      (node (ref "C580") (pin "1") (pinfunction "1_1") (pintype "passive"))
      (node (ref "C582") (pin "1") (pinfunction "1_1") (pintype "passive"))
      (node (ref "C583") (pin "1") (pinfunction "1_1") (pintype "passive"))
      (node (ref "C584") (pin "1") (pinfunction "1_1") (pintype "passive"))
      (node (ref "C585") (pin "1") (pinfunction "1_1") (pintype "passive"))
      (node (ref "C586") (pin "1") (pinfunction "1_1") (pintype "passive"))
      (node (ref "C587") (pin "1") (pinfunction "1_1") (pintype "passive"))
      (node (ref "C588") (pin "1") (pinfunction "1_1") (pintype "passive"))
      (node (ref "C589") (pin "1") (pinfunction "1_1") (pintype "passive"))
      (node (ref "C590") (pin "1") (pinfunction "1_1") (pintype "passive"))
      (node (ref "C592") (pin "1") (pinfunction "1_1") (pintype "passive"))
      (node (ref "C593") (pin "1") (pinfunction "1_1") (pintype "passive"))
      (node (ref "C594") (pin "1") (pinfunction "1_1") (pintype "passive"))
      (node (ref "C595") (pin "1") (pinfunction "1_1") (pintype "passive"))
      (node (ref "C596") (pin "1") (pinfunction "1_1") (pintype "passive"))
      (node (ref "C597") (pin "1") (pinfunction "1_1") (pintype "passive"))
      (node (ref "C598") (pin "1") (pinfunction "1_1") (pintype "passive"))
      (node (ref "C599") (pin "1") (pinfunction "1_1") (pintype "passive"))
      (node (ref "C600") (pin "1") (pinfunction "1_1") (pintype "passive"))
      (node (ref "C602") (pin "1") (pinfunction "1_1") (pintype "passive"))
      (node (ref "C603") (pin "1") (pinfunction "1_1") (pintype "passive"))
      (node (ref "C604") (pin "1") (pinfunction "1_1") (pintype "passive"))
      (node (ref "C605") (pin "1") (pinfunction "1_1") (pintype "passive"))
      (node (ref "C606") (pin "1") (pinfunction "1_1") (pintype "passive"))
      (node (ref "C607") (pin "1") (pinfunction "1_1") (pintype "passive"))
      (node (ref "C608") (pin "1") (pinfunction "1_1") (pintype "passive"))
      (node (ref "C609") (pin "1") (pinfunction "1_1") (pintype "passive"))
      (node (ref "C610") (pin "1") (pinfunction "1_1") (pintype "passive"))
      (node (ref "C612") (pin "1") (pinfunction "1_1") (pintype "passive"))
      (node (ref "C613") (pin "1") (pinfunction "1_1") (pintype "passive"))
      (node (ref "C614") (pin "1") (pinfunction "1_1") (pintype "passive"))
      (node (ref "C615") (pin "1") (pinfunction "1_1") (pintype "passive"))
      (node (ref "C616") (pin "1") (pinfunction "1_1") (pintype "passive"))
      (node (ref "C617") (pin "1") (pinfunction "1_1") (pintype "passive"))
      (node (ref "C618") (pin "1") (pinfunction "1_1") (pintype "passive"))
      (node (ref "C619") (pin "1") (pinfunction "1_1") (pintype "passive"))
      (node (ref "C620") (pin "1") (pinfunction "1_1") (pintype "passive"))
      (node (ref "C621") (pin "1") (pinfunction "1_1") (pintype "passive"))
      (node (ref "C622") (pin "1") (pinfunction "1_1") (pintype "passive"))
      (node (ref "C623") (pin "1") (pinfunction "1_1") (pintype "passive"))
      (node (ref "C624") (pin "1") (pinfunction "1_1") (pintype "passive"))
      (node (ref "C625") (pin "1") (pinfunction "1_1") (pintype "passive"))
      (node (ref "C626") (pin "1") (pinfunction "1_1") (pintype "passive"))
      (node (ref "C627") (pin "1") (pinfunction "1_1") (pintype "passive"))
      (node (ref "C628") (pin "1") (pinfunction "1_1") (pintype "passive"))
      (node (ref "C629") (pin "1") (pinfunction "1_1") (pintype "passive"))
      (node (ref "C630") (pin "1") (pinfunction "1_1") (pintype "passive"))
      (node (ref "C631") (pin "1") (pinfunction "1_1") (pintype "passive"))
      (node (ref "R309") (pin "2") (pinfunction "2_2") (pintype "passive"))
      (node (ref "R310") (pin "2") (pinfunction "2_2") (pintype "passive"))
      (node (ref "R311") (pin "2") (pinfunction "2_2") (pintype "passive"))
      (node (ref "R312") (pin "2") (pinfunction "2_2") (pintype "passive"))
      (node (ref "R313") (pin "2") (pinfunction "2_2") (pintype "passive"))
      (node (ref "R314") (pin "2") (pinfunction "2_2") (pintype "passive"))
      (node (ref "R315") (pin "2") (pinfunction "2_2") (pintype "passive"))
      (node (ref "R316") (pin "2") (pinfunction "2_2") (pintype "passive"))
      (node (ref "R366") (pin "2") (pinfunction "2_2") (pintype "passive"))
      (node (ref "R367") (pin "2") (pinfunction "2_2") (pintype "passive"))
      (node (ref "R371") (pin "2") (pinfunction "2_2") (pintype "passive"))
      (node (ref "R372") (pin "2") (pinfunction "2_2") (pintype "passive"))
      (node (ref "U60") (pin "C4") (pinfunction "VSS0_C4") (pintype "power_in"))
      (node (ref "U60") (pin "C8") (pinfunction "VSS1_C8") (pintype "power_in"))
      (node (ref "U60") (pin "D4") (pinfunction "VSS2_D4") (pintype "power_in"))
      (node (ref "U60") (pin "D5") (pinfunction "VSS3_D5") (pintype "power_in"))
      (node (ref "U60") (pin "D6") (pinfunction "VSS4_D6") (pintype "power_in"))
      (node (ref "U60") (pin "D7") (pinfunction "VSS5_D7") (pintype "power_in"))
      (node (ref "U60") (pin "D8") (pinfunction "VSS6_D8") (pintype "power_in"))
      (node (ref "U60") (pin "E5") (pinfunction "VSS7_E5") (pintype "power_in"))
      (node (ref "U60") (pin "E6") (pinfunction "VSS8_E6") (pintype "power_in"))
      (node (ref "U60") (pin "E7") (pinfunction "VSS9_E7") (pintype "power_in"))
      (node (ref "U60") (pin "F6") (pinfunction "VSS10_F6") (pintype "power_in"))
      (node (ref "U60") (pin "G6") (pinfunction "VSS11_G6") (pintype "power_in"))
      (node (ref "U60") (pin "H6") (pinfunction "VSS12_H6") (pintype "power_in"))
      (node (ref "U60") (pin "J6") (pinfunction "VSS13_J6") (pintype "power_in"))
      (node (ref "U60") (pin "K6") (pinfunction "VSS14_K6") (pintype "power_in"))
      (node (ref "U60") (pin "L5") (pinfunction "VSS15_L5") (pintype "power_in"))
      (node (ref "U60") (pin "L6") (pinfunction "VSS16_L6") (pintype "power_in"))
      (node (ref "U60") (pin "L7") (pinfunction "VSS17_L7") (pintype "power_in"))
      (node (ref "U60") (pin "M4") (pinfunction "VSS18_M4") (pintype "power_in"))
      (node (ref "U60") (pin "M5") (pinfunction "VSS19_M5") (pintype "power_in"))
      (node (ref "U60") (pin "M6") (pinfunction "VSS20_M6") (pintype "power_in"))
      (node (ref "U60") (pin "M7") (pinfunction "VSS21_M7") (pintype "power_in"))
      (node (ref "U60") (pin "M8") (pinfunction "VSS22_M8") (pintype "power_in"))
      (node (ref "U60") (pin "N4") (pinfunction "VSS23_N4") (pintype "power_in"))
      (node (ref "U60") (pin "N8") (pinfunction "VSS24_N8") (pintype "power_in"))
      (node (ref "U61") (pin "C4") (pinfunction "VSS0_C4") (pintype "power_in"))
      (node (ref "U61") (pin "C8") (pinfunction "VSS1_C8") (pintype "power_in"))
      (node (ref "U61") (pin "D4") (pinfunction "VSS2_D4") (pintype "power_in"))
      (node (ref "U61") (pin "D5") (pinfunction "VSS3_D5") (pintype "power_in"))
      (node (ref "U61") (pin "D6") (pinfunction "VSS4_D6") (pintype "power_in"))
      (node (ref "U61") (pin "D7") (pinfunction "VSS5_D7") (pintype "power_in"))
      (node (ref "U61") (pin "D8") (pinfunction "VSS6_D8") (pintype "power_in"))
      (node (ref "U61") (pin "E5") (pinfunction "VSS7_E5") (pintype "power_in"))
      (node (ref "U61") (pin "E6") (pinfunction "VSS8_E6") (pintype "power_in"))
      (node (ref "U61") (pin "E7") (pinfunction "VSS9_E7") (pintype "power_in"))
      (node (ref "U61") (pin "F6") (pinfunction "VSS10_F6") (pintype "power_in"))
      (node (ref "U61") (pin "G6") (pinfunction "VSS11_G6") (pintype "power_in"))
      (node (ref "U61") (pin "H6") (pinfunction "VSS12_H6") (pintype "power_in"))
      (node (ref "U61") (pin "J6") (pinfunction "VSS13_J6") (pintype "power_in"))
      (node (ref "U61") (pin "K6") (pinfunction "VSS14_K6") (pintype "power_in"))
      (node (ref "U61") (pin "L5") (pinfunction "VSS15_L5") (pintype "power_in"))
      (node (ref "U61") (pin "L6") (pinfunction "VSS16_L6") (pintype "power_in"))
      (node (ref "U61") (pin "L7") (pinfunction "VSS17_L7") (pintype "power_in"))
      (node (ref "U61") (pin "M4") (pinfunction "VSS18_M4") (pintype "power_in"))
      (node (ref "U61") (pin "M5") (pinfunction "VSS19_M5") (pintype "power_in"))
      (node (ref "U61") (pin "M6") (pinfunction "VSS20_M6") (pintype "power_in"))
      (node (ref "U61") (pin "M7") (pinfunction "VSS21_M7") (pintype "power_in"))
      (node (ref "U61") (pin "M8") (pinfunction "VSS22_M8") (pintype "power_in"))
      (node (ref "U61") (pin "N4") (pinfunction "VSS23_N4") (pintype "power_in"))
      (node (ref "U61") (pin "N8") (pinfunction "VSS24_N8") (pintype "power_in"))
      (node (ref "U62") (pin "11") (pinfunction "PPAD_11") (pintype "passive"))
      (node (ref "U62") (pin "4") (pinfunction "PGND_4") (pintype "passive"))
      (node (ref "U62") (pin "8") (pinfunction "GND_8") (pintype "passive"))
    )
    (net (code "228") (name "Net-(U60A-CQ#)") (class "Default")
      (node (ref "R399") (pin "1") (pinfunction "1_1") (pintype "passive"))
      (node (ref "U60") (pin "A1") (pinfunction "CQ#_A1") (pintype "output"))
    )
    (net (code "229") (name "Net-(U60A-CQ)") (class "Default")
      (node (ref "R398") (pin "1") (pinfunction "1_1") (pintype "passive"))
      (node (ref "U60") (pin "A11") (pinfunction "CQ_A11") (pintype "output"))
    )
    (net (code "230") (name "Net-(U60A-ODT)") (class "Default")
      (node (ref "R364") (pin "1") (pinfunction "1_1") (pintype "passive"))
      (node (ref "R366") (pin "1") (pinfunction "1_1") (pintype "passive"))
      (node (ref "U60") (pin "R6") (pinfunction "ODT_R6") (pintype "passive"))
    )
    (net (code "231") (name "Net-(U60A-QVLD)") (class "Default")
      (node (ref "R397") (pin "1") (pinfunction "1_1") (pintype "passive"))
      (node (ref "U60") (pin "P6") (pinfunction "QVLD_P6") (pintype "output"))
    )
    (net (code "232") (name "Net-(U60A-ZQ)") (class "Default")
      (node (ref "R371") (pin "1") (pinfunction "1_1") (pintype "passive"))
      (node (ref "U60") (pin "H11") (pinfunction "ZQ_H11") (pintype "passive"))
    )
    (net (code "233") (name "Net-(U61A-CQ#)") (class "Default")
      (node (ref "R417") (pin "1") (pinfunction "1_1") (pintype "passive"))
      (node (ref "U61") (pin "A1") (pinfunction "CQ#_A1") (pintype "output"))
    )
    (net (code "234") (name "Net-(U61A-CQ)") (class "Default")
      (node (ref "R411") (pin "1") (pinfunction "1_1") (pintype "passive"))
      (node (ref "U61") (pin "A11") (pinfunction "CQ_A11") (pintype "output"))
    )
    (net (code "235") (name "Net-(U61A-ODT)") (class "Default")
      (node (ref "R365") (pin "1") (pinfunction "1_1") (pintype "passive"))
      (node (ref "R367") (pin "1") (pinfunction "1_1") (pintype "passive"))
      (node (ref "U61") (pin "R6") (pinfunction "ODT_R6") (pintype "passive"))
    )
    (net (code "236") (name "Net-(U61A-QVLD)") (class "Default")
      (node (ref "R401") (pin "1") (pinfunction "1_1") (pintype "passive"))
      (node (ref "U61") (pin "P6") (pinfunction "QVLD_P6") (pintype "output"))
    )
    (net (code "237") (name "Net-(U61A-ZQ)") (class "Default")
      (node (ref "R372") (pin "1") (pinfunction "1_1") (pintype "passive"))
      (node (ref "U61") (pin "H11") (pinfunction "ZQ_H11") (pintype "passive"))
    )
    (net (code "238") (name "Net-(U62-S3)") (class "Default")
      (node (ref "R374") (pin "2") (pinfunction "2_2") (pintype "passive"))
      (node (ref "U62") (pin "7") (pinfunction "S3_7") (pintype "input"))
    )
    (net (code "239") (name "Net-(U62-S5)") (class "Default")
      (node (ref "R375") (pin "2") (pinfunction "2_2") (pintype "passive"))
      (node (ref "U62") (pin "9") (pinfunction "S5_9") (pintype "input"))
    )
    (net (code "240") (name "QDR23_VREF") (class "Default")
      (node (ref "C629") (pin "2") (pinfunction "2_2") (pintype "passive"))
      (node (ref "U60") (pin "H10") (pinfunction "VREF0_H10") (pintype "power_in"))
      (node (ref "U60") (pin "H2") (pinfunction "VREF1_H2") (pintype "power_in"))
      (node (ref "U61") (pin "H10") (pinfunction "VREF0_H10") (pintype "power_in"))
      (node (ref "U61") (pin "H2") (pinfunction "VREF1_H2") (pintype "power_in"))
      (node (ref "U62") (pin "6") (pinfunction "VTTREF_6") (pintype "output"))
    )
    (net (code "241") (name "QDR23_VTT") (class "Default")
      (node (ref "C612") (pin "2") (pinfunction "2_2") (pintype "passive"))
      (node (ref "C613") (pin "2") (pinfunction "2_2") (pintype "passive"))
      (node (ref "C614") (pin "2") (pinfunction "2_2") (pintype "passive"))
      (node (ref "C615") (pin "2") (pinfunction "2_2") (pintype "passive"))
      (node (ref "C616") (pin "2") (pinfunction "2_2") (pintype "passive"))
      (node (ref "C617") (pin "2") (pinfunction "2_2") (pintype "passive"))
      (node (ref "C618") (pin "2") (pinfunction "2_2") (pintype "passive"))
      (node (ref "C619") (pin "2") (pinfunction "2_2") (pintype "passive"))
      (node (ref "C620") (pin "2") (pinfunction "2_2") (pintype "passive"))
      (node (ref "C621") (pin "2") (pinfunction "2_2") (pintype "passive"))
      (node (ref "C622") (pin "2") (pinfunction "2_2") (pintype "passive"))
      (node (ref "C623") (pin "2") (pinfunction "2_2") (pintype "passive"))
      (node (ref "C624") (pin "2") (pinfunction "2_2") (pintype "passive"))
      (node (ref "C625") (pin "2") (pinfunction "2_2") (pintype "passive"))
      (node (ref "C628") (pin "2") (pinfunction "2_2") (pintype "passive"))
      (node (ref "C630") (pin "2") (pinfunction "2_2") (pintype "passive"))
      (node (ref "C631") (pin "2") (pinfunction "2_2") (pintype "passive"))
      (node (ref "R278") (pin "2") (pinfunction "2_2") (pintype "passive"))
      (node (ref "R279") (pin "2") (pinfunction "2_2") (pintype "passive"))
      (node (ref "R280") (pin "2") (pinfunction "2_2") (pintype "passive"))
      (node (ref "R281") (pin "2") (pinfunction "2_2") (pintype "passive"))
      (node (ref "R282") (pin "2") (pinfunction "2_2") (pintype "passive"))
      (node (ref "R283") (pin "2") (pinfunction "2_2") (pintype "passive"))
      (node (ref "RP17") (pin "5") (pinfunction "5_5") (pintype "passive"))
      (node (ref "RP17") (pin "6") (pinfunction "6_6") (pintype "passive"))
      (node (ref "RP17") (pin "7") (pinfunction "7_7") (pintype "passive"))
      (node (ref "RP17") (pin "8") (pinfunction "8_8") (pintype "passive"))
      (node (ref "RP18") (pin "5") (pinfunction "5_5") (pintype "passive"))
      (node (ref "RP18") (pin "6") (pinfunction "6_6") (pintype "passive"))
      (node (ref "RP18") (pin "7") (pinfunction "7_7") (pintype "passive"))
      (node (ref "RP18") (pin "8") (pinfunction "8_8") (pintype "passive"))
      (node (ref "RP19") (pin "5") (pinfunction "5_5") (pintype "passive"))
      (node (ref "RP19") (pin "6") (pinfunction "6_6") (pintype "passive"))
      (node (ref "RP19") (pin "7") (pinfunction "7_7") (pintype "passive"))
      (node (ref "RP19") (pin "8") (pinfunction "8_8") (pintype "passive"))
      (node (ref "RP20") (pin "5") (pinfunction "5_5") (pintype "passive"))
      (node (ref "RP20") (pin "6") (pinfunction "6_6") (pintype "passive"))
      (node (ref "RP20") (pin "7") (pinfunction "7_7") (pintype "passive"))
      (node (ref "RP20") (pin "8") (pinfunction "8_8") (pintype "passive"))
      (node (ref "RP21") (pin "5") (pinfunction "5_5") (pintype "passive"))
      (node (ref "RP21") (pin "6") (pinfunction "6_6") (pintype "passive"))
      (node (ref "RP21") (pin "7") (pinfunction "7_7") (pintype "passive"))
      (node (ref "RP21") (pin "8") (pinfunction "8_8") (pintype "passive"))
      (node (ref "RP22") (pin "5") (pinfunction "5_5") (pintype "passive"))
      (node (ref "RP22") (pin "6") (pinfunction "6_6") (pintype "passive"))
      (node (ref "RP22") (pin "7") (pinfunction "7_7") (pintype "passive"))
      (node (ref "RP22") (pin "8") (pinfunction "8_8") (pintype "passive"))
      (node (ref "RP23") (pin "5") (pinfunction "5_5") (pintype "passive"))
      (node (ref "RP23") (pin "6") (pinfunction "6_6") (pintype "passive"))
      (node (ref "RP23") (pin "7") (pinfunction "7_7") (pintype "passive"))
      (node (ref "RP23") (pin "8") (pinfunction "8_8") (pintype "passive"))
      (node (ref "RP24") (pin "5") (pinfunction "5_5") (pintype "passive"))
      (node (ref "RP24") (pin "6") (pinfunction "6_6") (pintype "passive"))
      (node (ref "RP24") (pin "7") (pinfunction "7_7") (pintype "passive"))
      (node (ref "RP24") (pin "8") (pinfunction "8_8") (pintype "passive"))
      (node (ref "RP25") (pin "5") (pinfunction "5_5") (pintype "passive"))
      (node (ref "RP25") (pin "6") (pinfunction "6_6") (pintype "passive"))
      (node (ref "RP25") (pin "7") (pinfunction "7_7") (pintype "passive"))
      (node (ref "RP25") (pin "8") (pinfunction "8_8") (pintype "passive"))
      (node (ref "RP26") (pin "5") (pinfunction "5_5") (pintype "passive"))
      (node (ref "RP26") (pin "6") (pinfunction "6_6") (pintype "passive"))
      (node (ref "RP26") (pin "7") (pinfunction "7_7") (pintype "passive"))
      (node (ref "RP26") (pin "8") (pinfunction "8_8") (pintype "passive"))
      (node (ref "U62") (pin "3") (pinfunction "VTT_3") (pintype "output"))
      (node (ref "U62") (pin "5") (pinfunction "VTTSNS_5") (pintype "input"))
    )
    (net (code "242") (name "unconnected-(U60D-NC1-PadC6)") (class "Default")
      (node (ref "U60") (pin "C6") (pinfunction "NC1_C6") (pintype "passive+no_connect"))
    )
    (net (code "243") (name "unconnected-(U61D-NC1-PadC6)") (class "Default")
      (node (ref "U61") (pin "C6") (pinfunction "NC1_C6") (pintype "passive+no_connect"))
    )
  )
)
